# MiniPrinterController.net
KiCad netlist of a schematic drawn in EAGLE
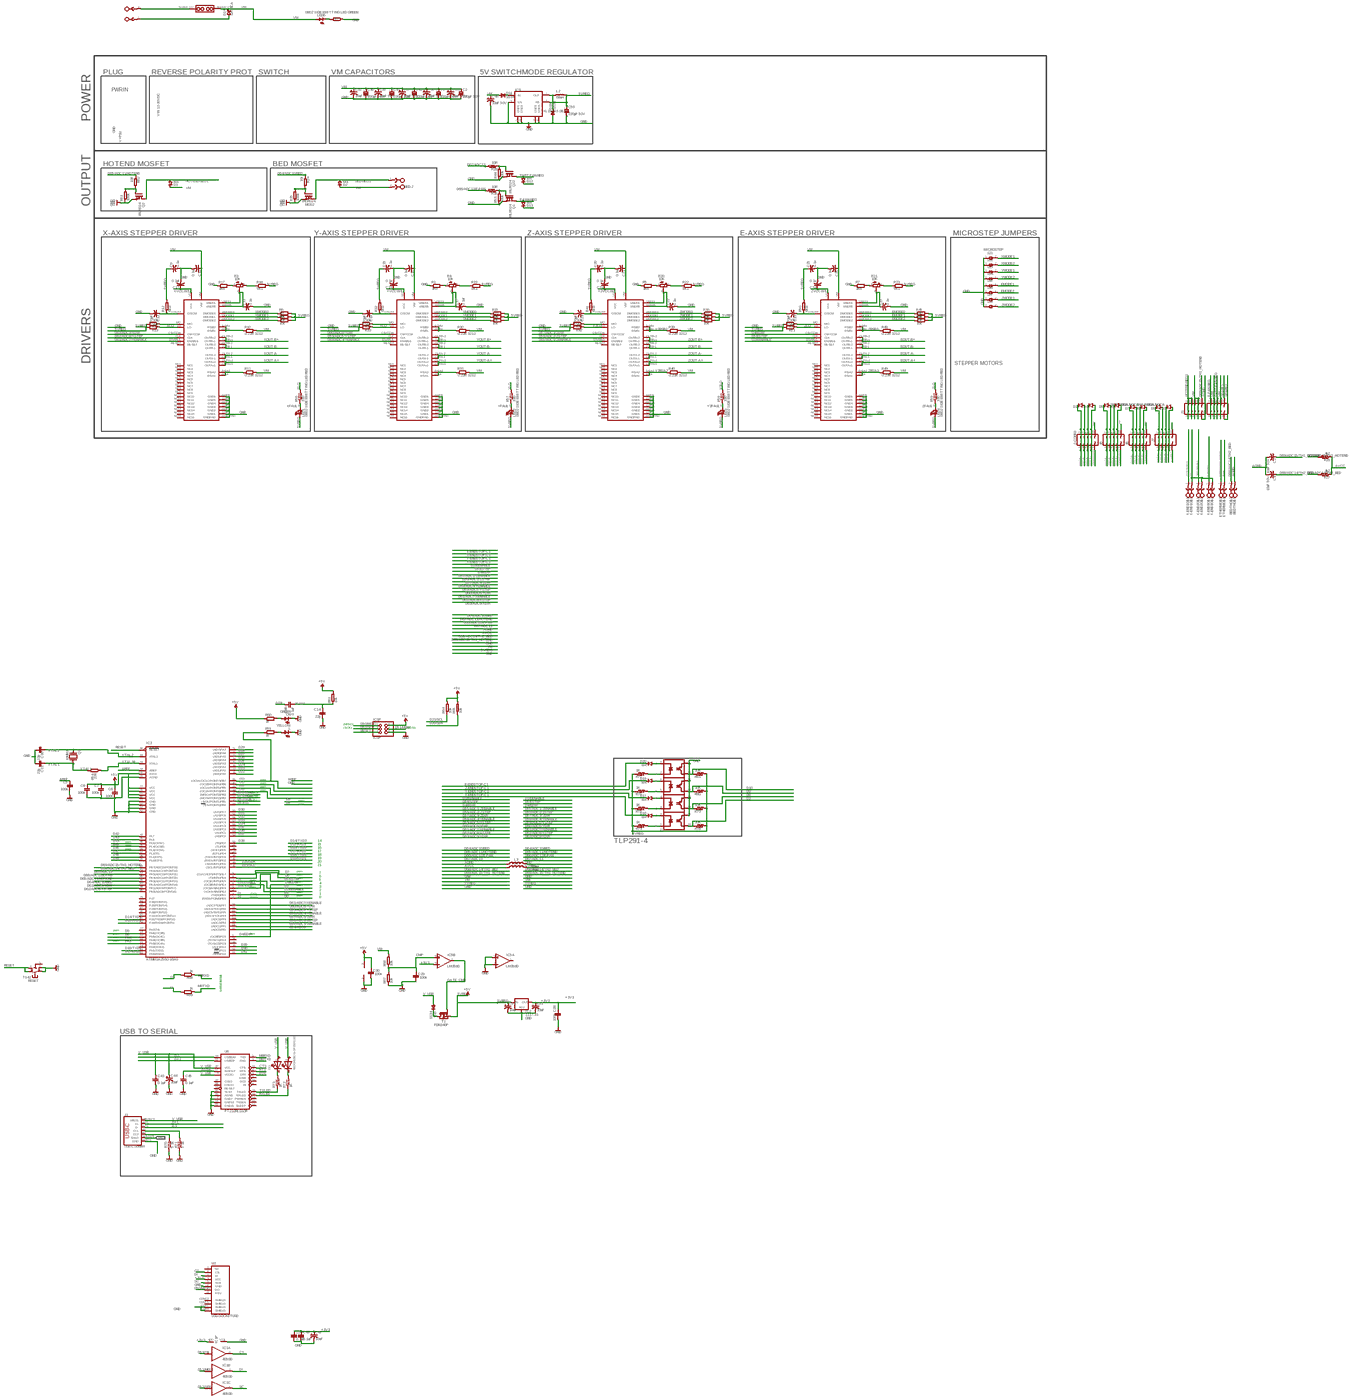
[diagram p0: schematic, sheet 1, overview]
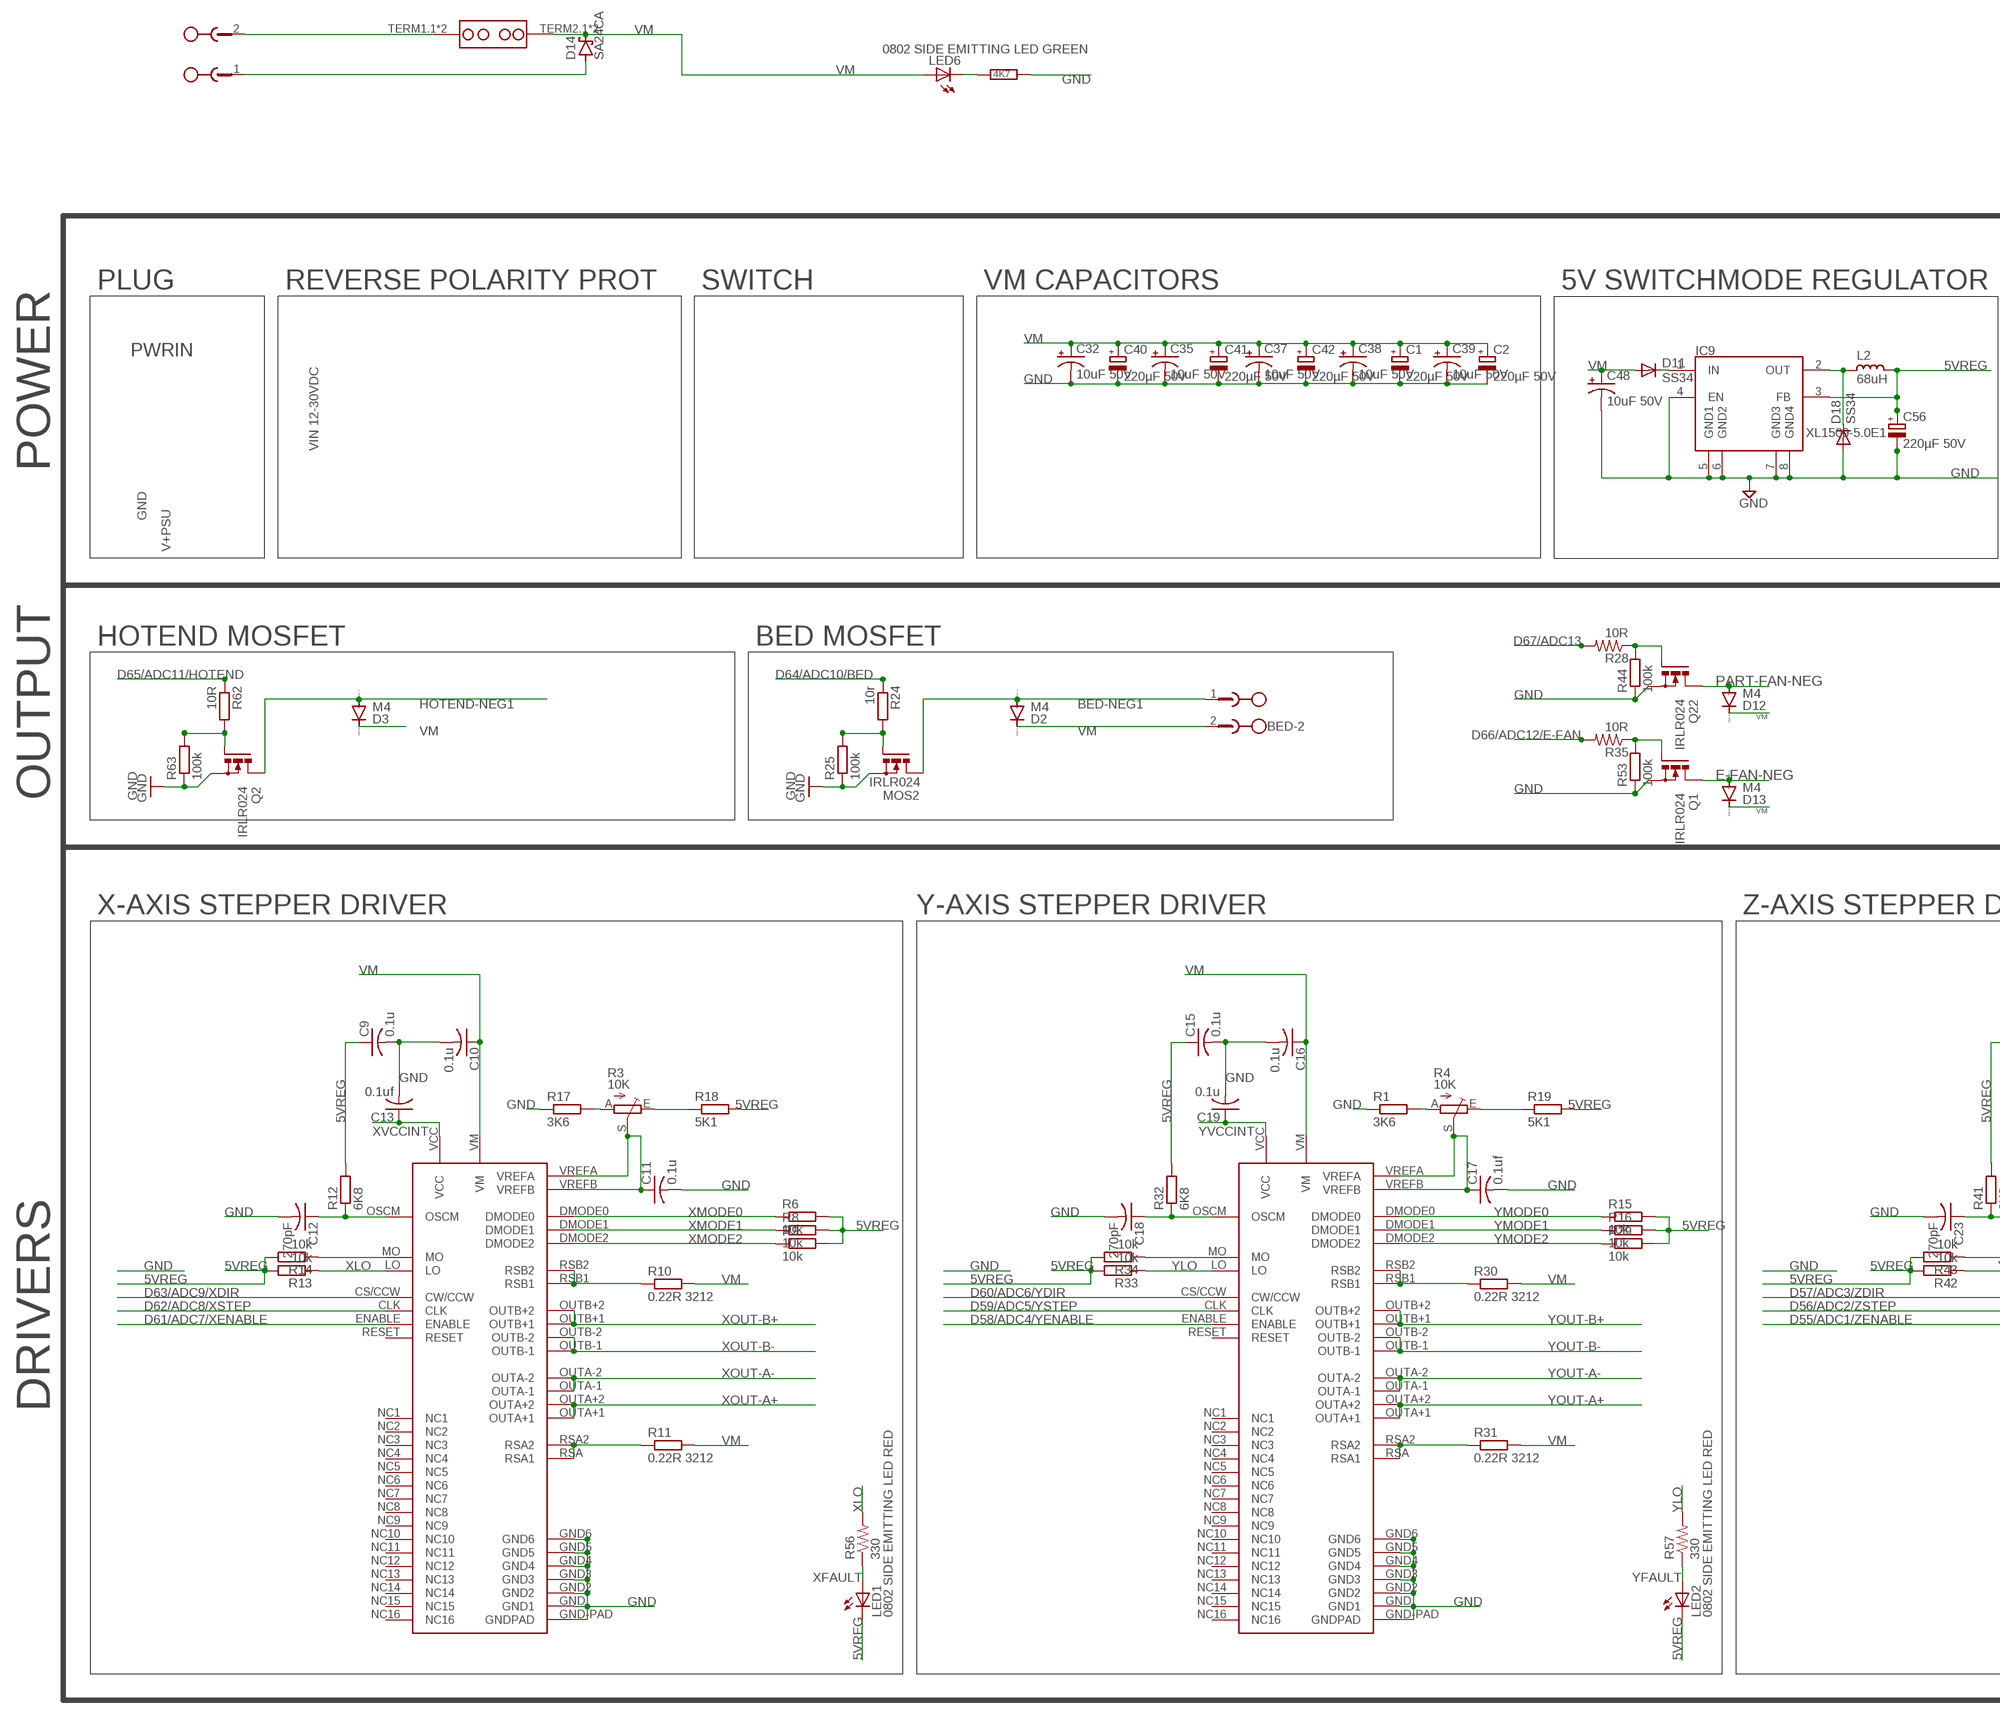
[diagram p1: schematic, sheet 1, part 1 of 7]
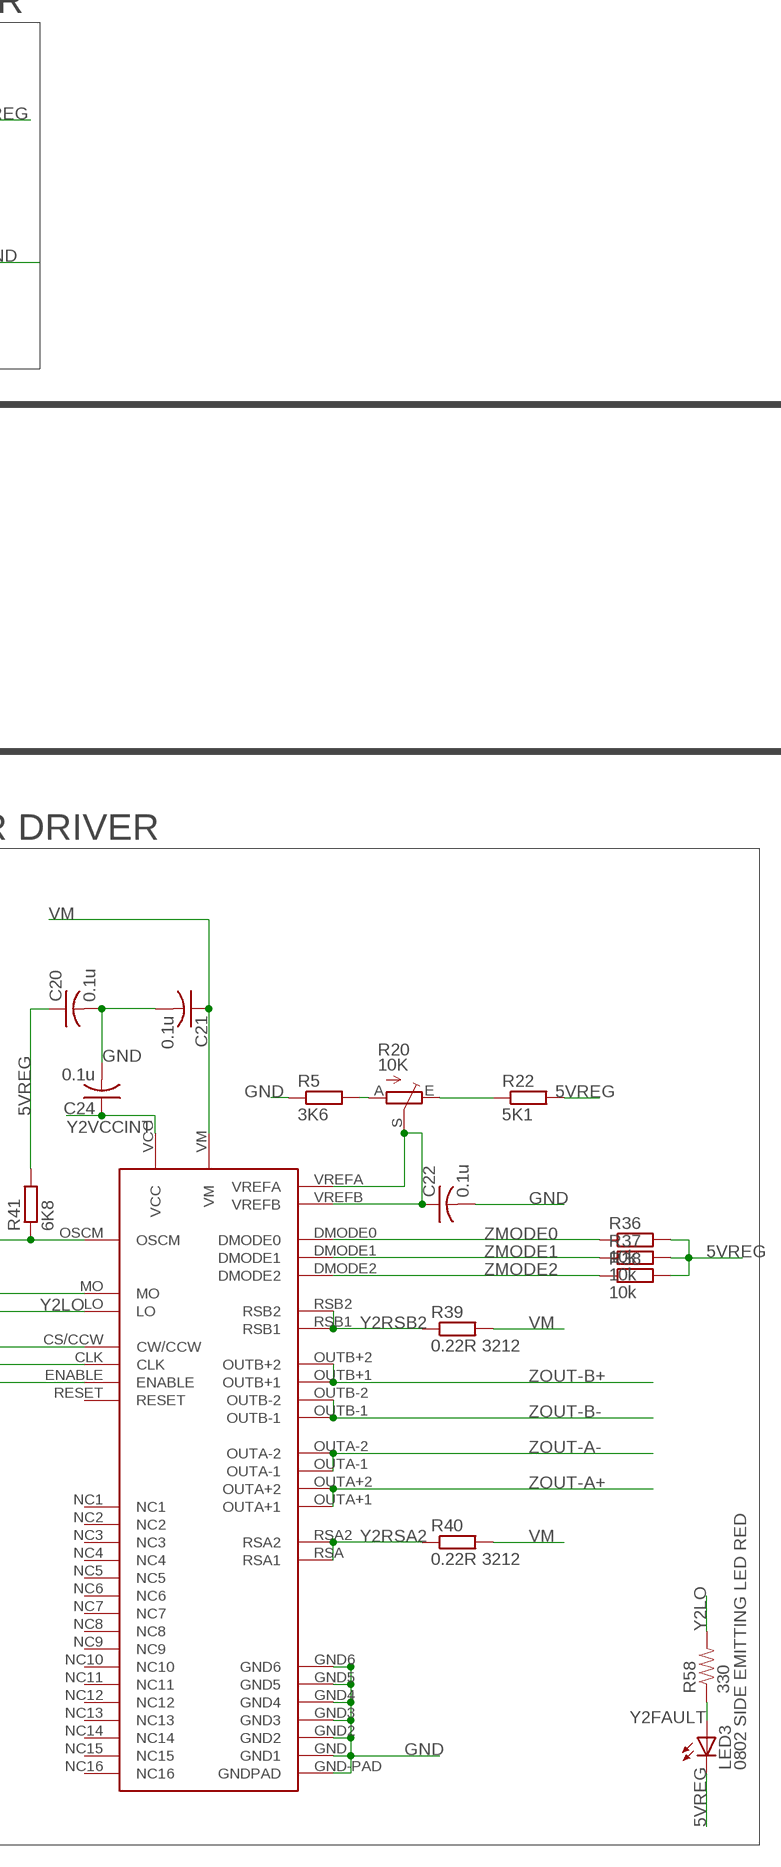
[diagram p2: schematic, sheet 1, part 2 of 7]
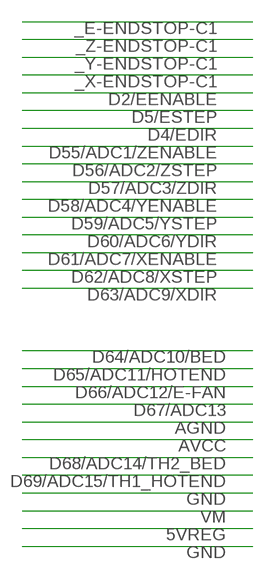
[diagram p3: schematic, sheet 1, part 3 of 7]
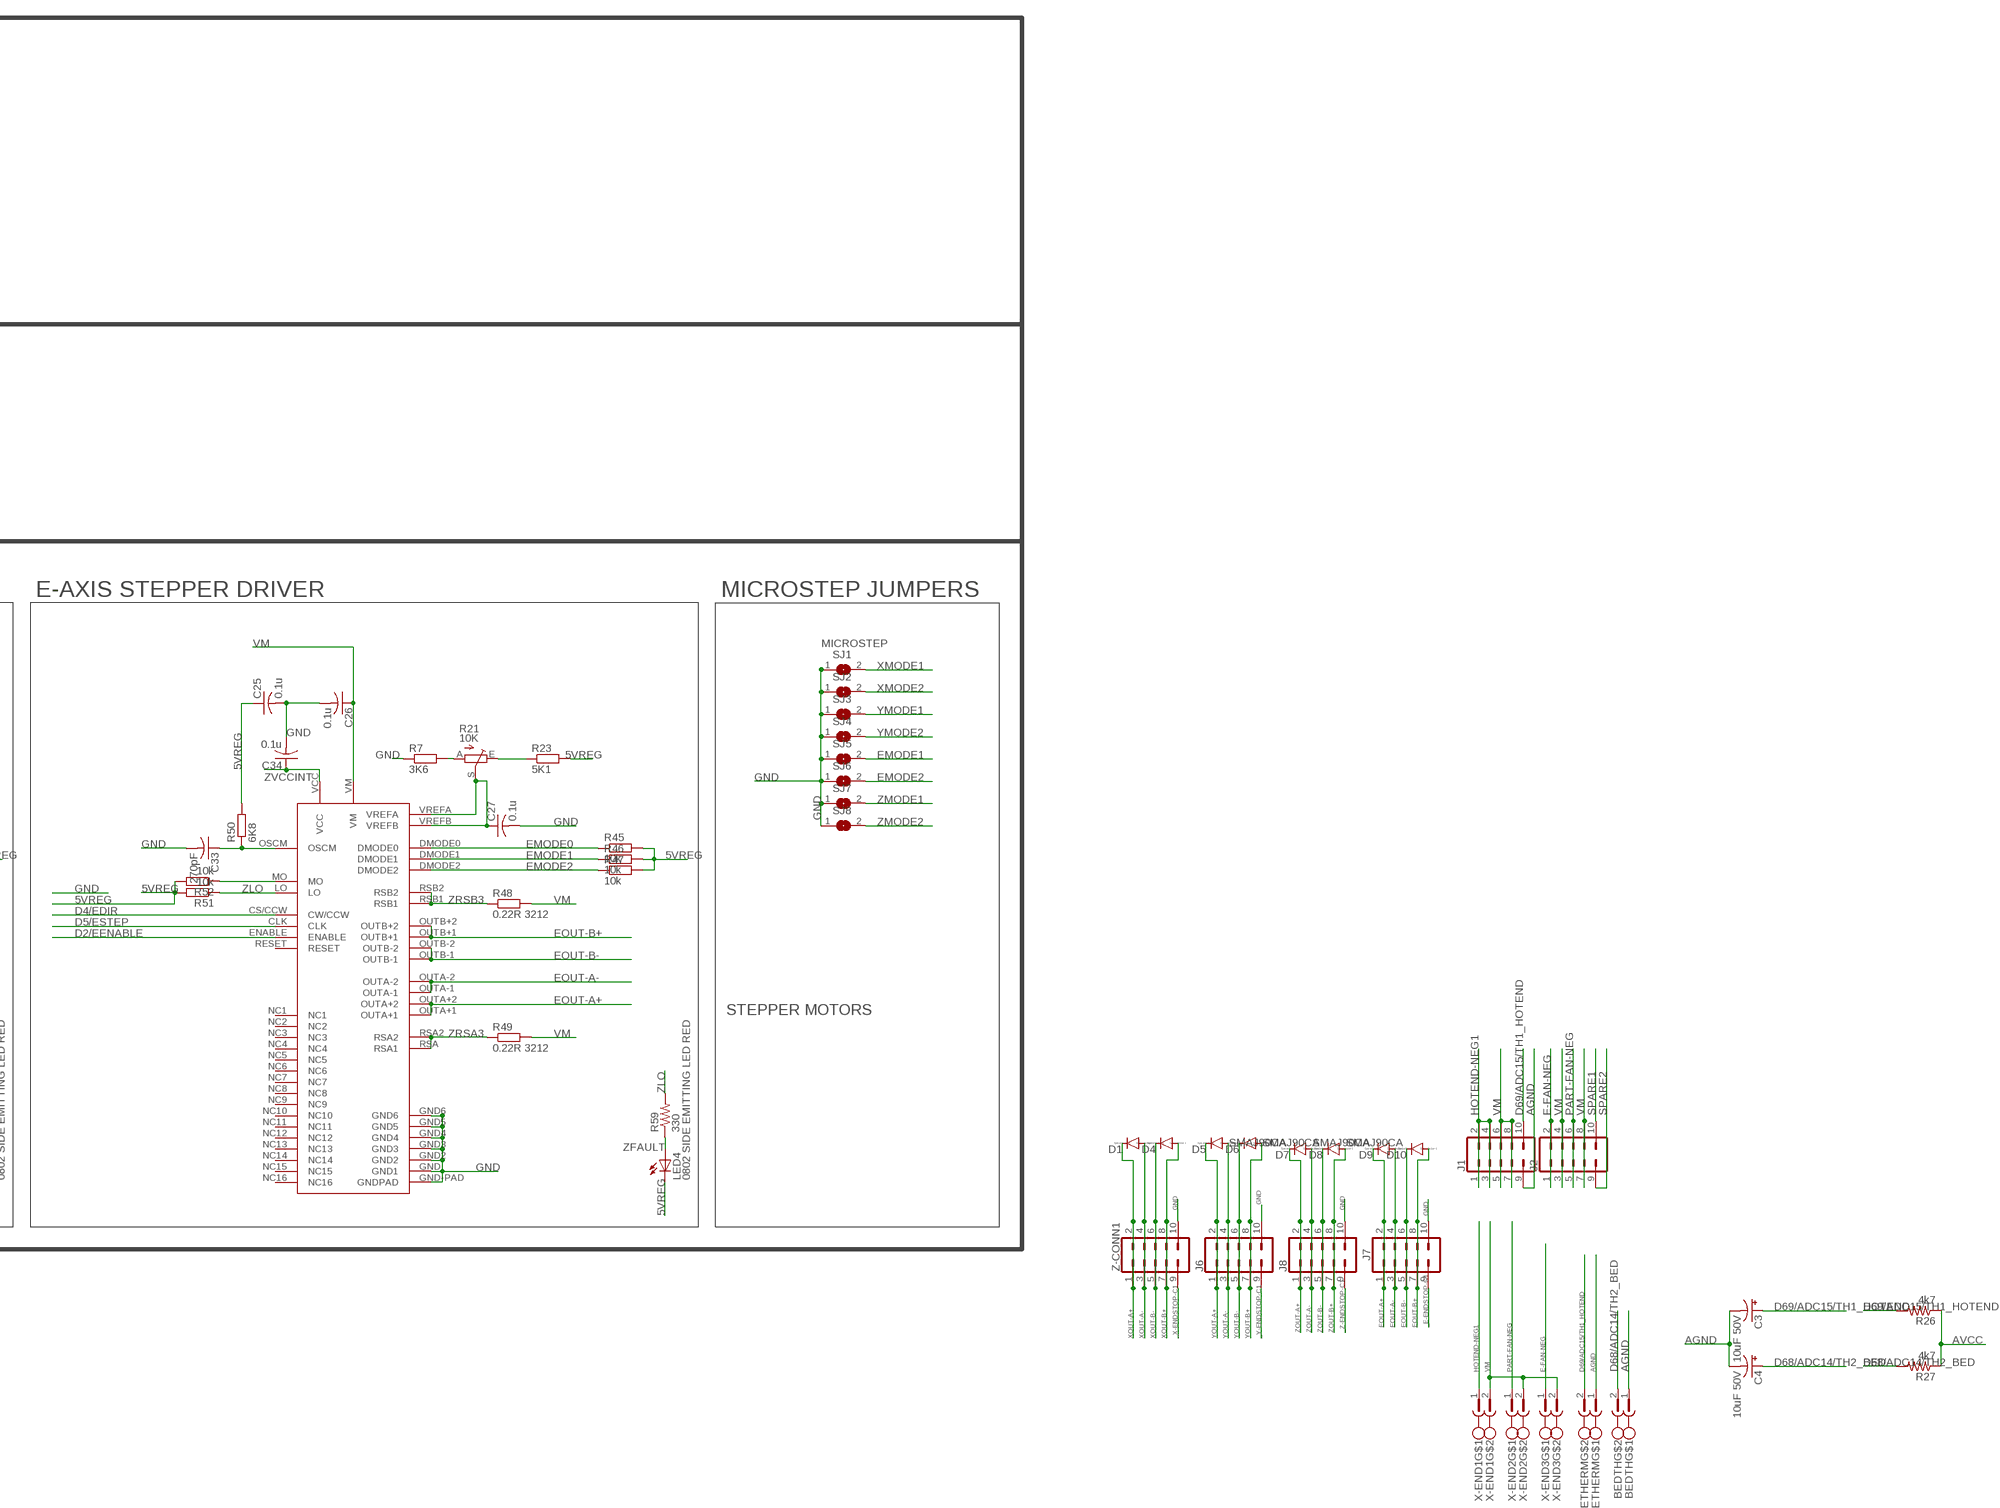
[diagram p4: schematic, sheet 1, part 4 of 7]
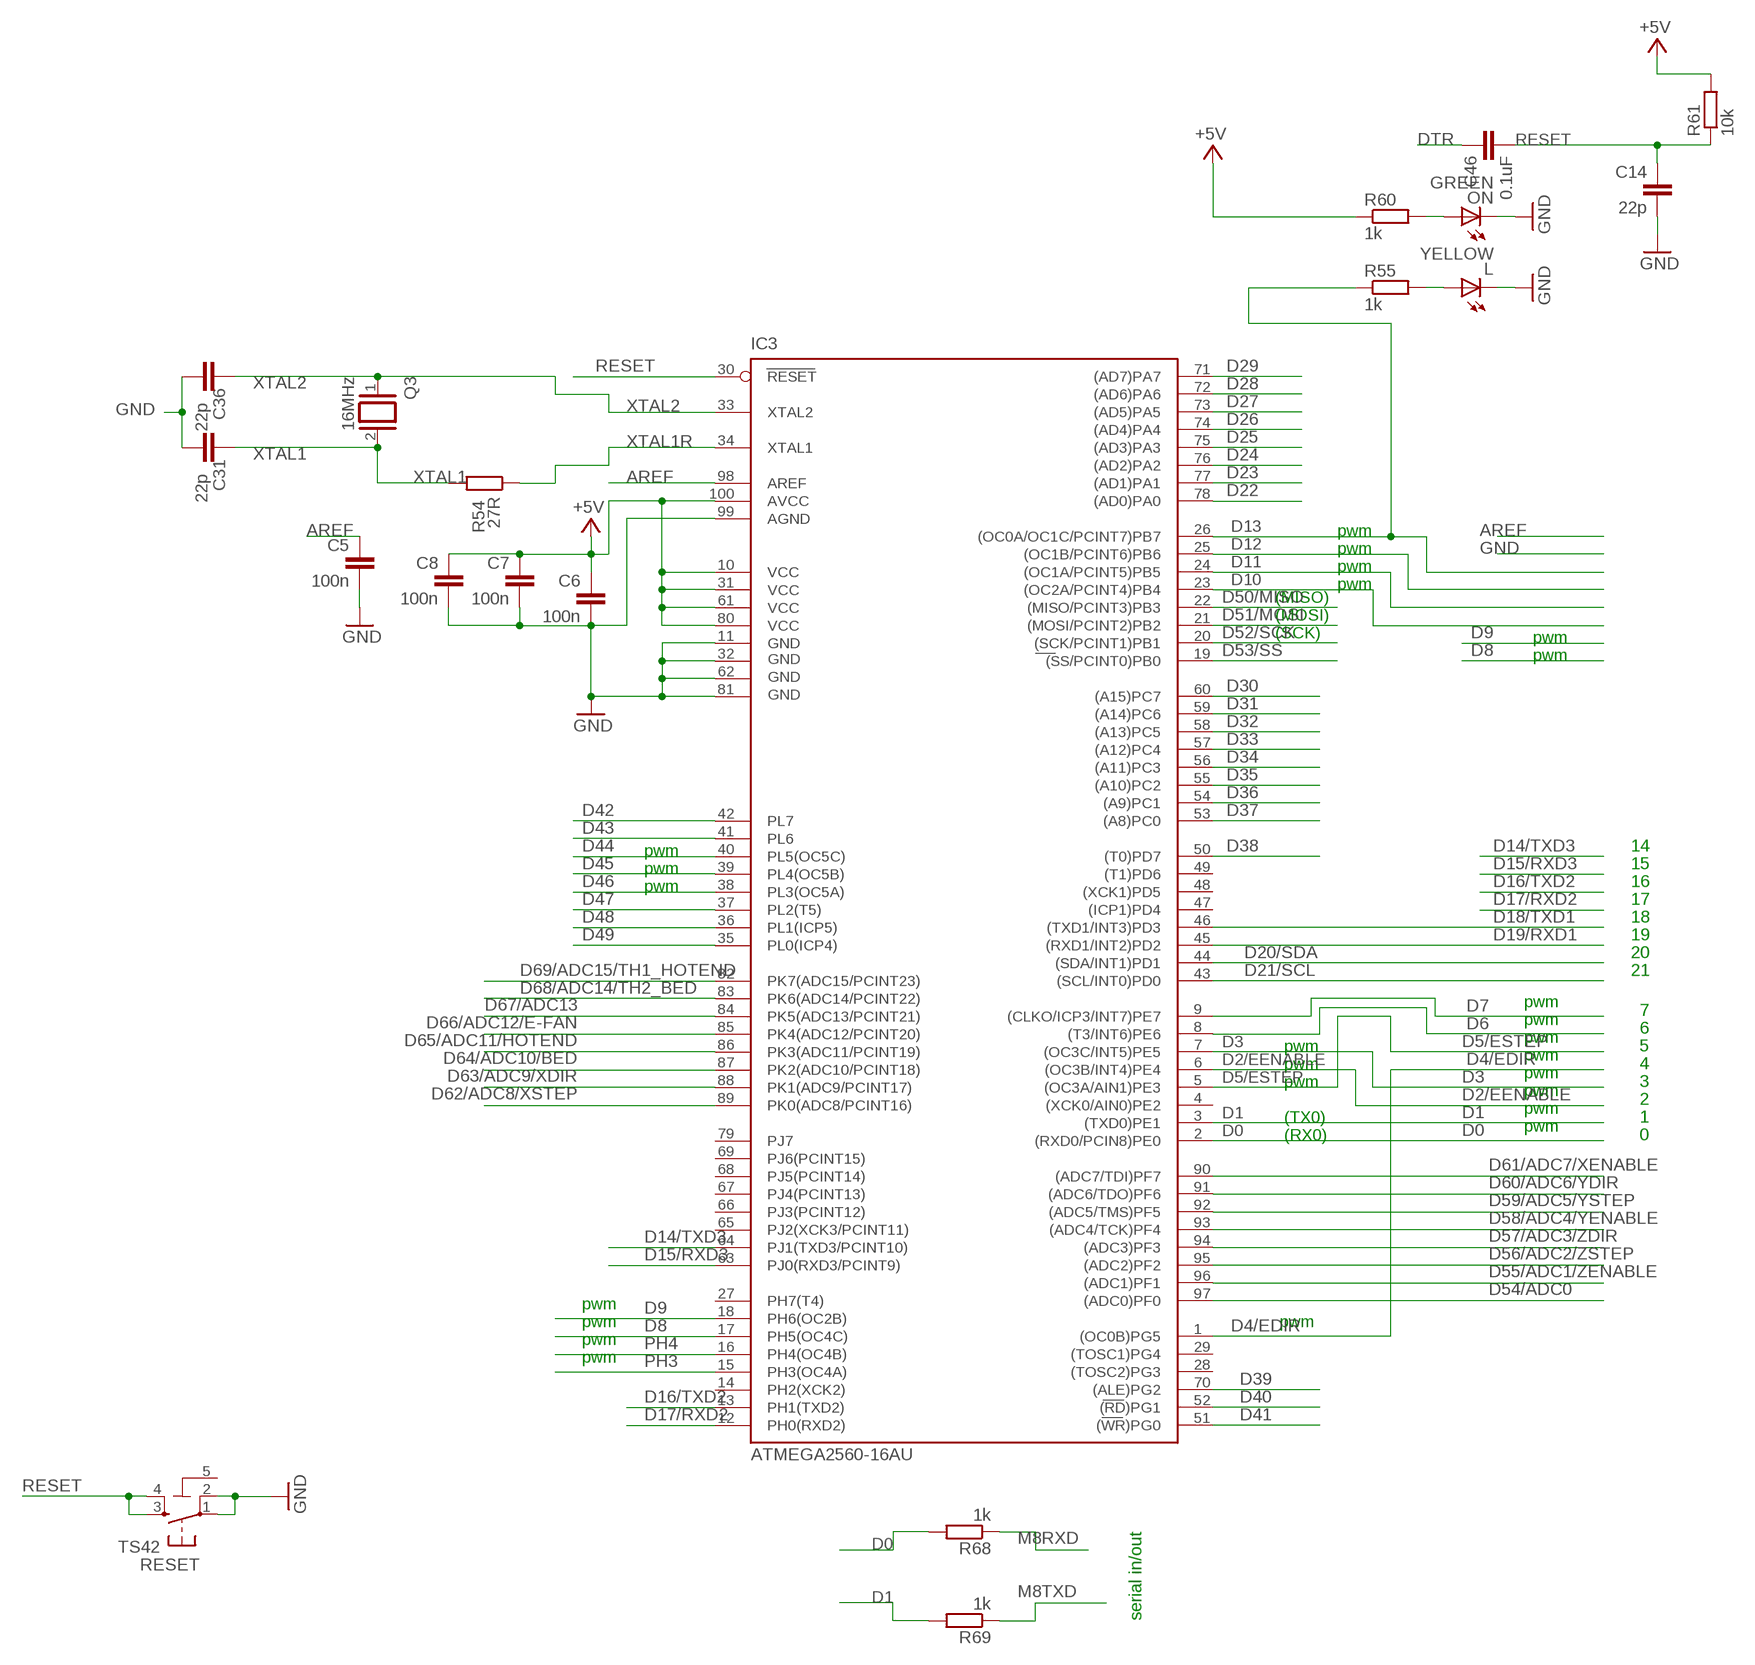
[diagram p5: schematic, sheet 1, part 5 of 7]
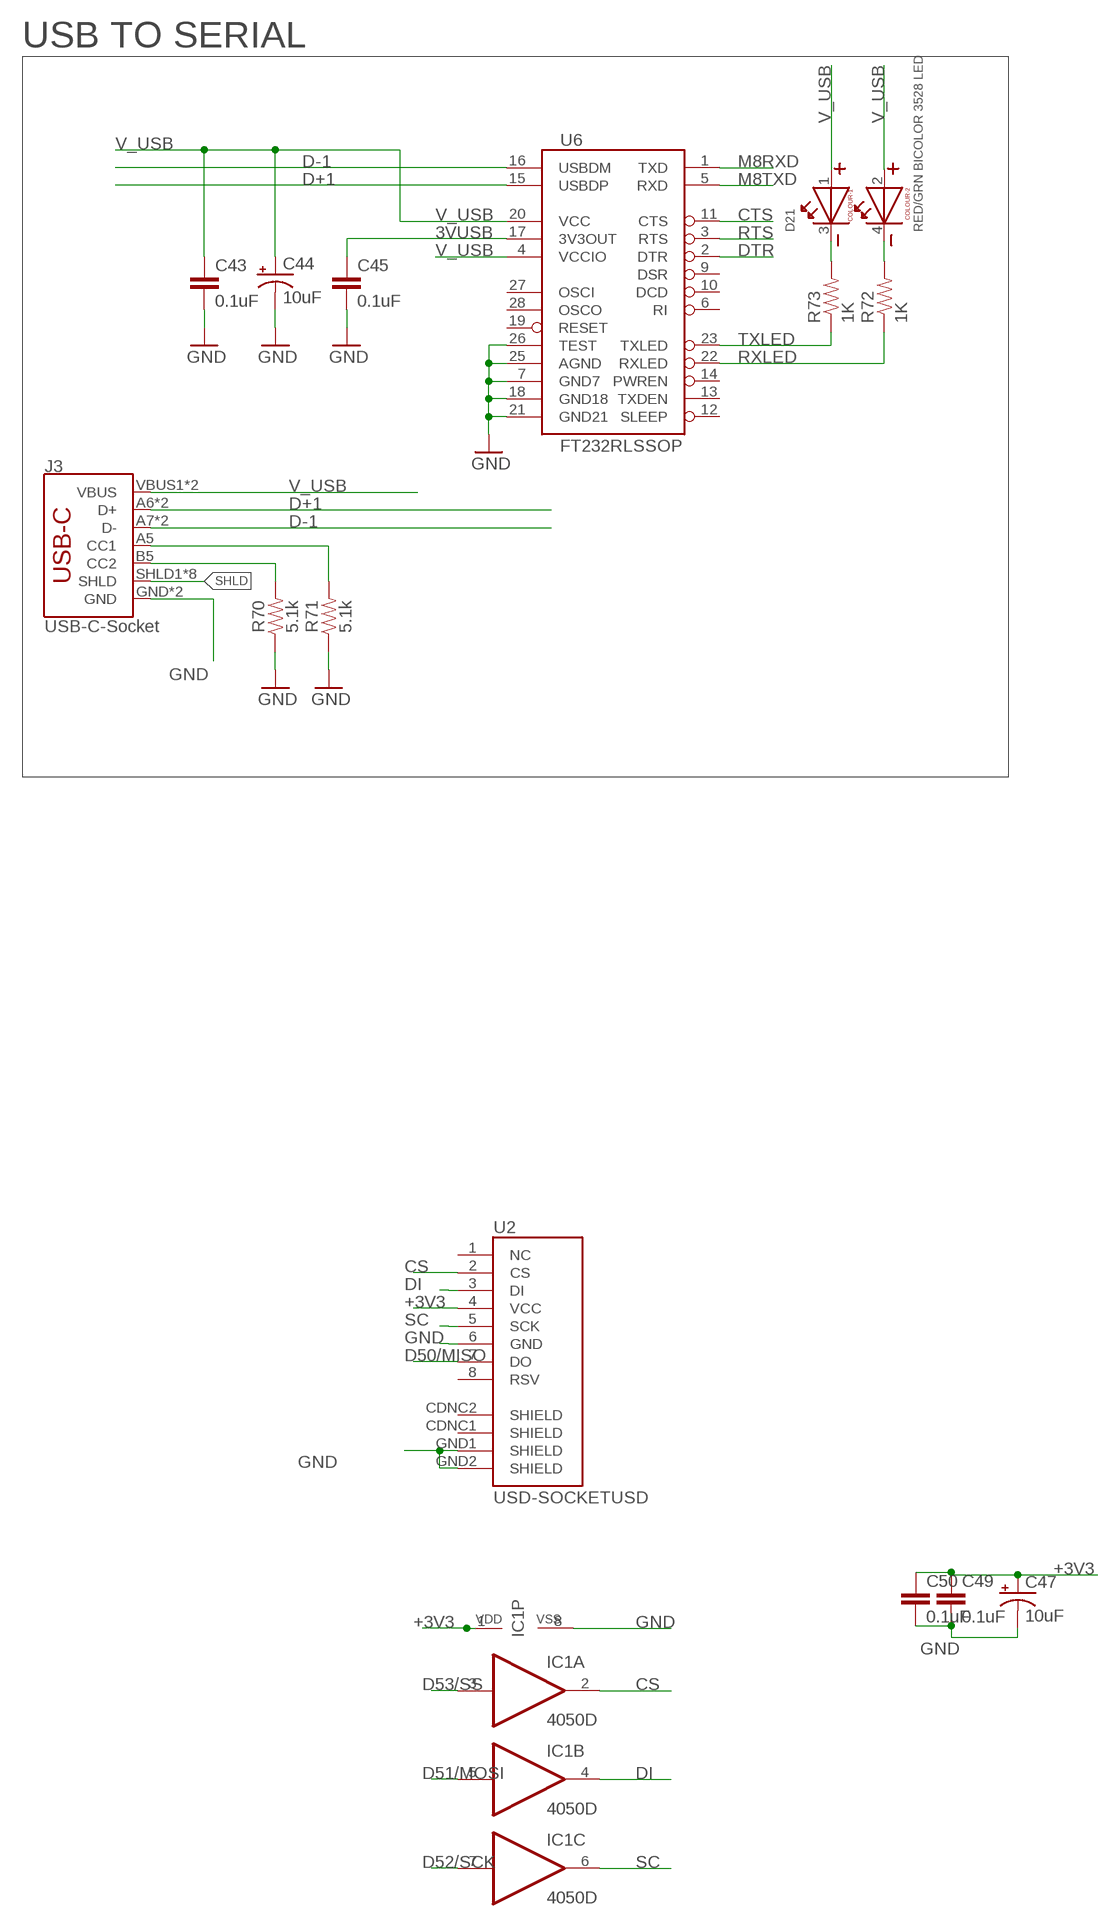
[diagram p6: schematic, sheet 1, part 6 of 7]
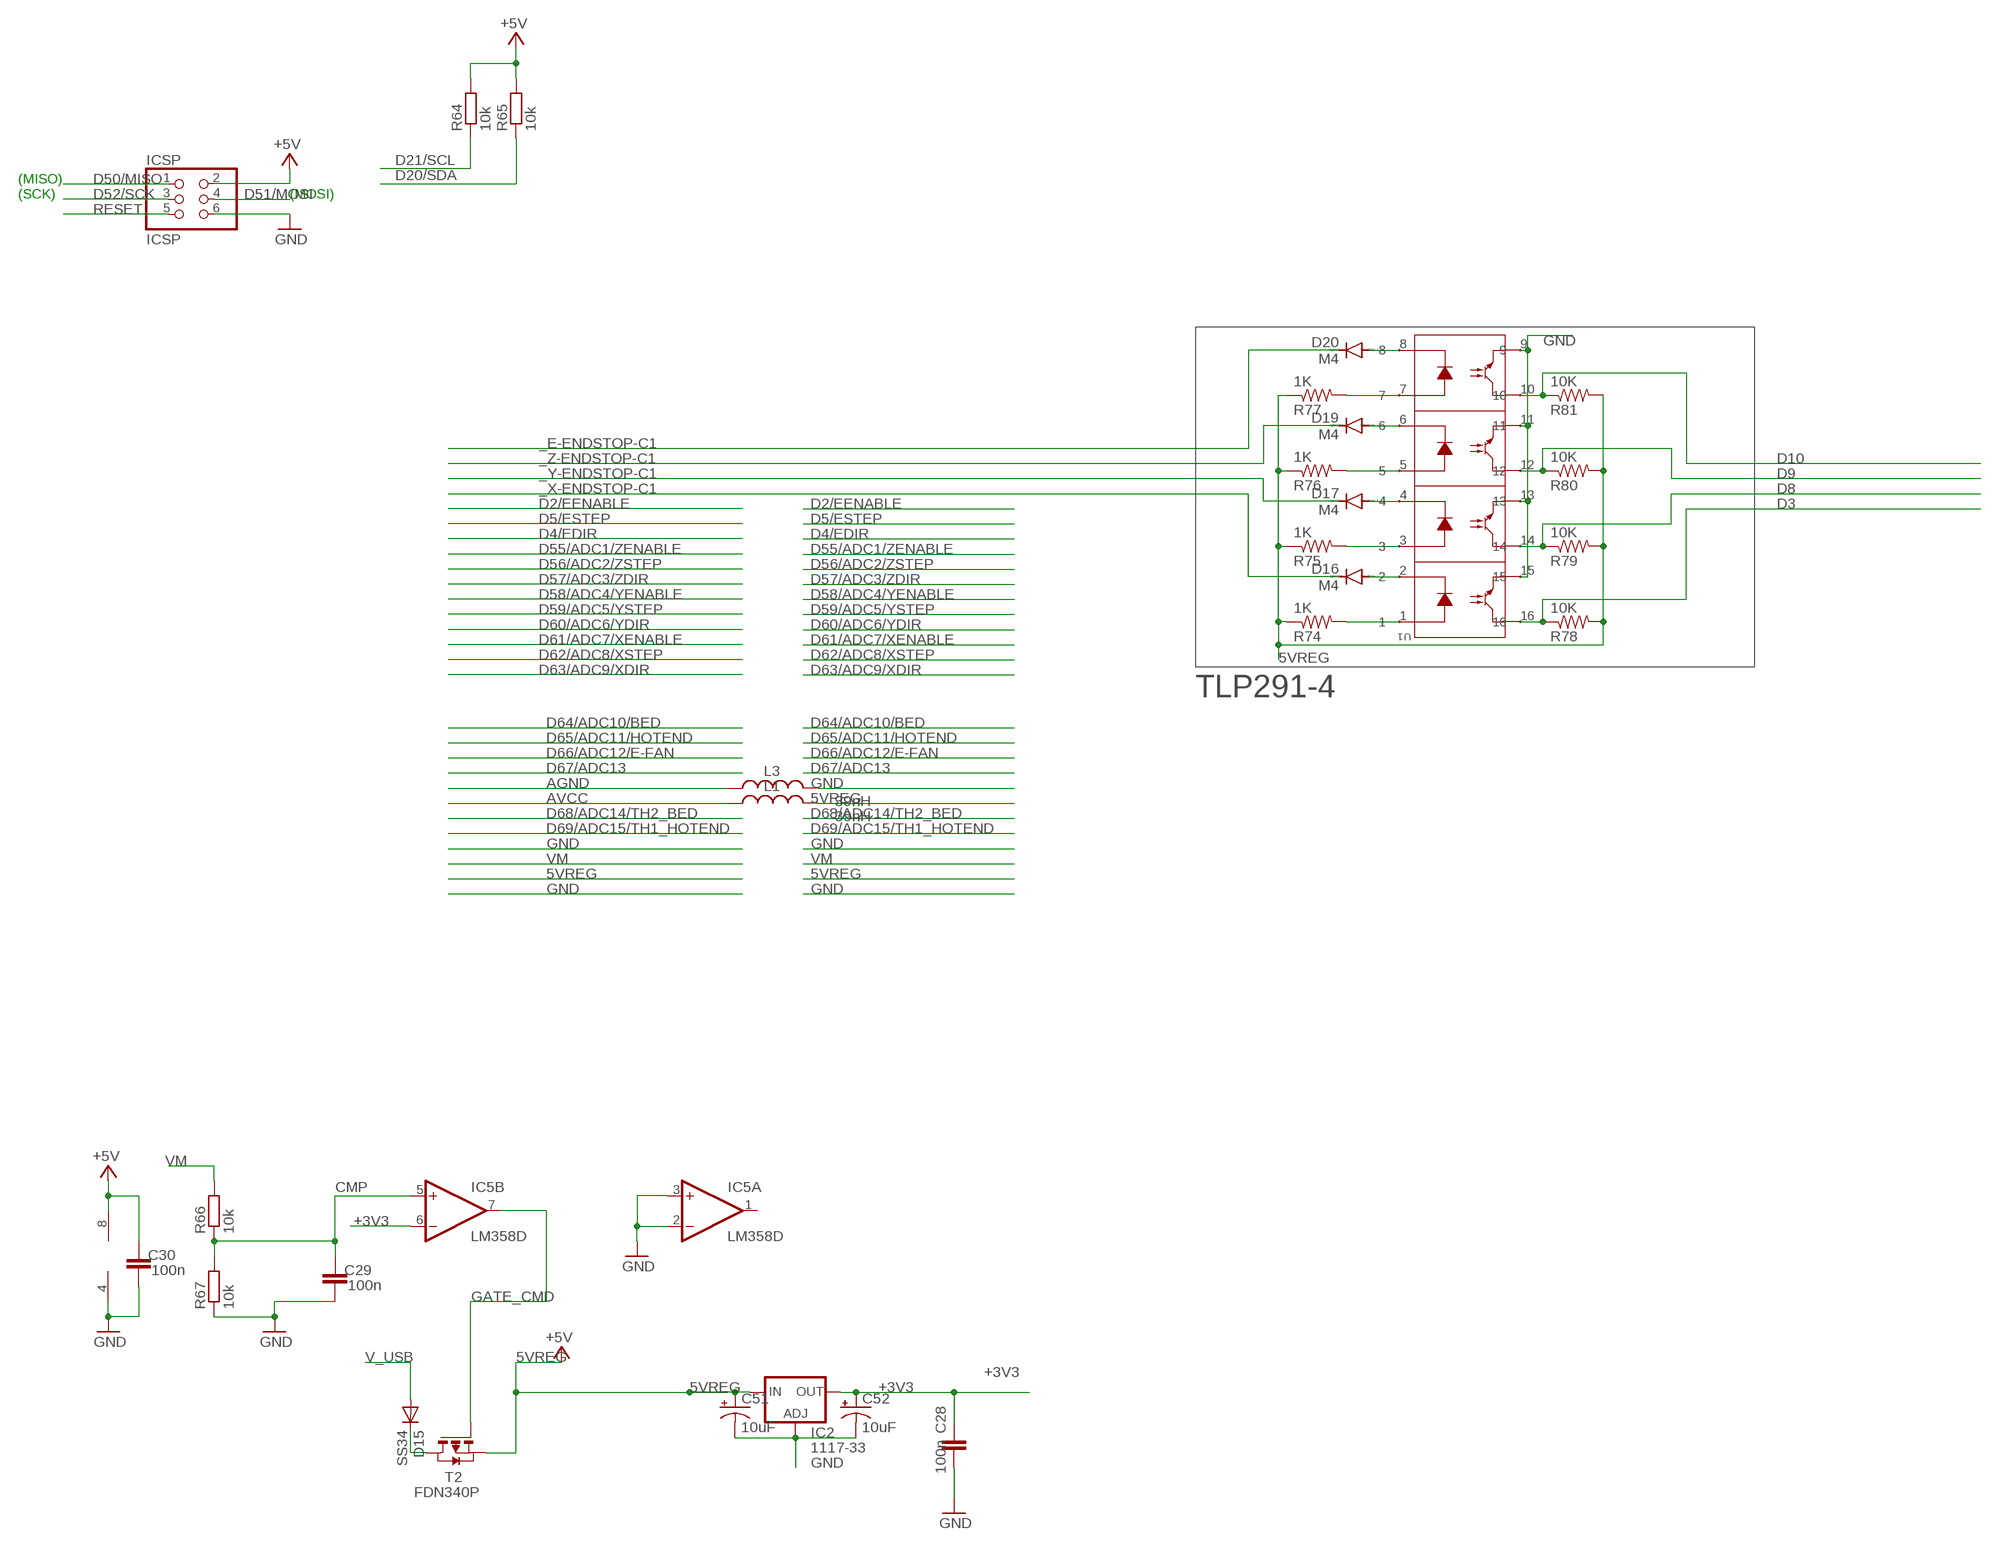
[diagram p7: schematic, sheet 1, part 7 of 7]

(export (version "E")
  (design (tool "Eeschema 10.0.6"))
  (components
    (comp (ref "BED")
      (value "Phoenix Pluggable 5.08mm 2 way")
      (footprint "eagle-import:MSTBA2")
      (fields (field (name "MF") "FARNELL") (field (name "MPN") "1757242"))
      (libsource (lib "eagle-import") (part "MSTBA2"))
    )
    (comp (ref "BEDTH")
      (value "Phoenix Pluggable 3.81mm 2 way")
      (footprint "eagle-import:MC1.5_2-G-3.81")
      (libsource (lib "eagle-import") (part "MC1.5/2"))
    )
    (comp (ref "C1")
      (value "220µF 50V")
      (footprint "eagle-import:E3,5-10")
      (libsource (lib "eagle-import") (part "CPOL-EUE3.5-10"))
    )
    (comp (ref "C2")
      (value "220µF 50V")
      (footprint "eagle-import:E3,5-10")
      (libsource (lib "eagle-import") (part "CPOL-EUE3.5-10"))
    )
    (comp (ref "C3")
      (value "10uF 50V")
      (footprint "eagle-import:EIA3216")
      (libsource (lib "eagle-import") (part "CAP_POL1206"))
    )
    (comp (ref "C4")
      (value "10uF 50V")
      (footprint "eagle-import:EIA3216")
      (libsource (lib "eagle-import") (part "CAP_POL1206"))
    )
    (comp (ref "C5")
      (value "100n")
      (footprint "eagle-import:C0603-ROUND")
      (libsource (lib "eagle-import") (part "C-EU0603-RND"))
    )
    (comp (ref "C6")
      (value "100n")
      (footprint "eagle-import:C0603-ROUND")
      (libsource (lib "eagle-import") (part "C-EU0603-RND"))
    )
    (comp (ref "C7")
      (value "100n")
      (footprint "eagle-import:C0603-ROUND")
      (libsource (lib "eagle-import") (part "C-EU0603-RND"))
    )
    (comp (ref "C8")
      (value "100n")
      (footprint "eagle-import:C0603-ROUND")
      (libsource (lib "eagle-import") (part "C-EU0603-RND"))
    )
    (comp (ref "C9")
      (value "0.1u")
      (footprint "eagle-import:C0603K")
      (libsource (lib "eagle-import") (part "C-USC0603K"))
    )
    (comp (ref "C10")
      (value "0.1u")
      (footprint "eagle-import:C0603K")
      (libsource (lib "eagle-import") (part "C-USC0603K"))
    )
    (comp (ref "C11")
      (value "0.1u")
      (footprint "eagle-import:C0603K")
      (libsource (lib "eagle-import") (part "C-USC0603K"))
    )
    (comp (ref "C12")
      (value "270pF")
      (footprint "eagle-import:C0603K")
      (libsource (lib "eagle-import") (part "C-USC0603K"))
    )
    (comp (ref "C13")
      (value "0.1uf")
      (footprint "eagle-import:C0603K")
      (libsource (lib "eagle-import") (part "C-USC0603K"))
    )
    (comp (ref "C14")
      (value "22p")
      (footprint "eagle-import:C0603-ROUND")
      (libsource (lib "eagle-import") (part "C-EU0603-RND"))
    )
    (comp (ref "C15")
      (value "0.1u")
      (footprint "eagle-import:C0603K")
      (libsource (lib "eagle-import") (part "C-USC0603K"))
    )
    (comp (ref "C16")
      (value "0.1u")
      (footprint "eagle-import:C0603K")
      (libsource (lib "eagle-import") (part "C-USC0603K"))
    )
    (comp (ref "C17")
      (value "0.1uf")
      (footprint "eagle-import:C0603K")
      (libsource (lib "eagle-import") (part "C-USC0603K"))
    )
    (comp (ref "C18")
      (value "270pF")
      (footprint "eagle-import:C0603K")
      (libsource (lib "eagle-import") (part "C-USC0603K"))
    )
    (comp (ref "C19")
      (value "0.1u")
      (footprint "eagle-import:C0603K")
      (libsource (lib "eagle-import") (part "C-USC0603K"))
    )
    (comp (ref "C20")
      (value "0.1u")
      (footprint "eagle-import:C0603K")
      (libsource (lib "eagle-import") (part "C-USC0603K"))
    )
    (comp (ref "C21")
      (value "0.1u")
      (footprint "eagle-import:C0603K")
      (libsource (lib "eagle-import") (part "C-USC0603K"))
    )
    (comp (ref "C22")
      (value "0.1u")
      (footprint "eagle-import:C0603K")
      (libsource (lib "eagle-import") (part "C-USC0603K"))
    )
    (comp (ref "C23")
      (value "270pF")
      (footprint "eagle-import:C0603K")
      (libsource (lib "eagle-import") (part "C-USC0603K"))
    )
    (comp (ref "C24")
      (value "0.1u")
      (footprint "eagle-import:C0603K")
      (libsource (lib "eagle-import") (part "C-USC0603K"))
    )
    (comp (ref "C25")
      (value "0.1u")
      (footprint "eagle-import:C0603K")
      (libsource (lib "eagle-import") (part "C-USC0603K"))
    )
    (comp (ref "C26")
      (value "0.1u")
      (footprint "eagle-import:C0603K")
      (libsource (lib "eagle-import") (part "C-USC0603K"))
    )
    (comp (ref "C27")
      (value "0.1u")
      (footprint "eagle-import:C0603K")
      (libsource (lib "eagle-import") (part "C-USC0603K"))
    )
    (comp (ref "C28")
      (value "100n")
      (footprint "eagle-import:C0603-ROUND")
      (libsource (lib "eagle-import") (part "C-EU0603-RND"))
    )
    (comp (ref "C29")
      (value "100n")
      (footprint "eagle-import:C0603-ROUND")
      (libsource (lib "eagle-import") (part "C-EU0603-RND"))
    )
    (comp (ref "C30")
      (value "100n")
      (footprint "eagle-import:C0603")
      (libsource (lib "eagle-import") (part "rcl_C-EUC0603"))
    )
    (comp (ref "C31")
      (value "22p")
      (footprint "eagle-import:C0603-ROUND")
      (libsource (lib "eagle-import") (part "C-EU0603-RND"))
    )
    (comp (ref "C32")
      (value "10uF 50V")
      (footprint "eagle-import:EIA3216")
      (libsource (lib "eagle-import") (part "CAP_POL1206"))
    )
    (comp (ref "C33")
      (value "270pF")
      (footprint "eagle-import:C0603K")
      (libsource (lib "eagle-import") (part "C-USC0603K"))
    )
    (comp (ref "C34")
      (value "0.1u")
      (footprint "eagle-import:C0603K")
      (libsource (lib "eagle-import") (part "C-USC0603K"))
    )
    (comp (ref "C35")
      (value "10uF 50V")
      (footprint "eagle-import:EIA3216")
      (libsource (lib "eagle-import") (part "CAP_POL1206"))
    )
    (comp (ref "C36")
      (value "22p")
      (footprint "eagle-import:C0603-ROUND")
      (libsource (lib "eagle-import") (part "C-EU0603-RND"))
    )
    (comp (ref "C37")
      (value "10uF 50V")
      (footprint "eagle-import:EIA3216")
      (libsource (lib "eagle-import") (part "CAP_POL1206"))
    )
    (comp (ref "C38")
      (value "10uF 50V")
      (footprint "eagle-import:EIA3216")
      (libsource (lib "eagle-import") (part "CAP_POL1206"))
    )
    (comp (ref "C39")
      (value "10uF 50V")
      (footprint "eagle-import:EIA3216")
      (libsource (lib "eagle-import") (part "CAP_POL1206"))
    )
    (comp (ref "C40")
      (value "220µF 50V")
      (footprint "eagle-import:E3,5-10")
      (libsource (lib "eagle-import") (part "CPOL-EUE3.5-10"))
    )
    (comp (ref "C41")
      (value "220µF 50V")
      (footprint "eagle-import:E3,5-10")
      (libsource (lib "eagle-import") (part "CPOL-EUE3.5-10"))
    )
    (comp (ref "C42")
      (value "220µF 50V")
      (footprint "eagle-import:E3,5-10")
      (libsource (lib "eagle-import") (part "CPOL-EUE3.5-10"))
    )
    (comp (ref "C43")
      (value "0.1uF")
      (footprint "eagle-import:0603-CAP")
      (libsource (lib "eagle-import") (part "CAP0603-CAP"))
    )
    (comp (ref "C44")
      (value "10uF")
      (footprint "eagle-import:EIA3216")
      (libsource (lib "eagle-import") (part "CAP_POL1206"))
    )
    (comp (ref "C45")
      (value "0.1uF")
      (footprint "eagle-import:0603-CAP")
      (libsource (lib "eagle-import") (part "CAP0603-CAP"))
    )
    (comp (ref "C46")
      (value "0.1uF")
      (footprint "eagle-import:C0603-ROUND")
      (libsource (lib "eagle-import") (part "C-EU0603-RND"))
    )
    (comp (ref "C47")
      (value "10uF")
      (footprint "eagle-import:EIA3216")
      (libsource (lib "eagle-import") (part "CAP_POL1206"))
    )
    (comp (ref "C48")
      (value "10uF 50V")
      (footprint "eagle-import:EIA3216")
      (libsource (lib "eagle-import") (part "CAP_POL1206"))
    )
    (comp (ref "C49")
      (value "0.1uF")
      (footprint "eagle-import:0603-CAP")
      (libsource (lib "eagle-import") (part "CAP0603-CAP"))
    )
    (comp (ref "C50")
      (value "0.1uF")
      (footprint "eagle-import:0603-CAP")
      (libsource (lib "eagle-import") (part "CAP0603-CAP"))
    )
    (comp (ref "C51")
      (value "10uF")
      (footprint "eagle-import:EIA3216")
      (libsource (lib "eagle-import") (part "CAP_POL1206"))
    )
    (comp (ref "C52")
      (value "10uF")
      (footprint "eagle-import:EIA3216")
      (libsource (lib "eagle-import") (part "CAP_POL1206"))
    )
    (comp (ref "C56")
      (value "220µF 50V")
      (footprint "eagle-import:E3,5-10")
      (libsource (lib "eagle-import") (part "CPOL-EUE3.5-10"))
    )
    (comp (ref "D1")
      (value "SMAJ90CA")
      (footprint "eagle-import:DO-214AC")
      (libsource (lib "eagle-import") (part "DIODE-DO-214AC"))
    )
    (comp (ref "D2")
      (value "M4")
      (footprint "eagle-import:DO-214AC")
      (libsource (lib "eagle-import") (part "DIODE-DO-214AC"))
    )
    (comp (ref "D3")
      (value "M4")
      (footprint "eagle-import:DO-214AC")
      (libsource (lib "eagle-import") (part "DIODE-DO-214AC"))
    )
    (comp (ref "D4")
      (value "SMAJ90CA")
      (footprint "eagle-import:DO-214AC")
      (libsource (lib "eagle-import") (part "DIODE-DO-214AC"))
    )
    (comp (ref "D5")
      (value "SMAJ90CA")
      (footprint "eagle-import:DO-214AC")
      (libsource (lib "eagle-import") (part "DIODE-DO-214AC"))
    )
    (comp (ref "D6")
      (value "SMAJ90CA")
      (footprint "eagle-import:DO-214AC")
      (libsource (lib "eagle-import") (part "DIODE-DO-214AC"))
    )
    (comp (ref "D7")
      (value "SMAJ90CA")
      (footprint "eagle-import:DO-214AC")
      (libsource (lib "eagle-import") (part "DIODE-DO-214AC"))
    )
    (comp (ref "D8")
      (value "SMAJ90CA")
      (footprint "eagle-import:DO-214AC")
      (libsource (lib "eagle-import") (part "DIODE-DO-214AC"))
    )
    (comp (ref "D9")
      (value "SMAJ90CA")
      (footprint "eagle-import:DO-214AC")
      (libsource (lib "eagle-import") (part "DIODE-DO-214AC"))
    )
    (comp (ref "D10")
      (value "SMAJ90CA")
      (footprint "eagle-import:DO-214AC")
      (libsource (lib "eagle-import") (part "DIODE-DO-214AC"))
    )
    (comp (ref "D11")
      (value "SS34")
      (footprint "eagle-import:DO-214AC")
      (libsource (lib "eagle-import") (part "dp_devices_DIODE-DO-214AC"))
    )
    (comp (ref "D12")
      (value "M4")
      (footprint "eagle-import:DO-214AC")
      (libsource (lib "eagle-import") (part "DIODE-DO-214AC"))
    )
    (comp (ref "D13")
      (value "M4")
      (footprint "eagle-import:DO-214AC")
      (libsource (lib "eagle-import") (part "DIODE-DO-214AC"))
    )
    (comp (ref "D14")
      (value "SA24CA")
      (footprint "eagle-import:C4111-15")
      (libsource (lib "eagle-import") (part "1N6267A"))
    )
    (comp (ref "D15")
      (value "SS34")
      (footprint "eagle-import:DO-214AC")
      (libsource (lib "eagle-import") (part "dp_devices_DIODE-DO-214AC"))
    )
    (comp (ref "D16")
      (value "M4")
      (footprint "eagle-import:DO-214AC")
      (libsource (lib "eagle-import") (part "DIODE-DO-214AC"))
    )
    (comp (ref "D17")
      (value "M4")
      (footprint "eagle-import:DO-214AC")
      (libsource (lib "eagle-import") (part "DIODE-DO-214AC"))
    )
    (comp (ref "D18")
      (value "SS34")
      (footprint "eagle-import:DO-214AC")
      (libsource (lib "eagle-import") (part "dp_devices_DIODE-DO-214AC"))
    )
    (comp (ref "D19")
      (value "M4")
      (footprint "eagle-import:DO-214AC")
      (libsource (lib "eagle-import") (part "DIODE-DO-214AC"))
    )
    (comp (ref "D20")
      (value "M4")
      (footprint "eagle-import:DO-214AC")
      (libsource (lib "eagle-import") (part "DIODE-DO-214AC"))
    )
    (comp (ref "D21")
      (value "RED/GRN BICOLOR 3528 LED")
      (footprint "eagle-import:3528")
      (fields
        (field (name "MANUFACTURER") "Würth Elektronik eiSos GmbH")
        (field (name "CREATED-BY") "Christin Otto")
      )
      (libsource (lib "eagle-import") (part "WL-SBTW-150141RB73100-R&B"))
    )
    (comp (ref "ETHERM")
      (value "Phoenix Pluggable 3.81mm 2 way")
      (footprint "eagle-import:MC1.5_2-G-3.81")
      (libsource (lib "eagle-import") (part "MC1.5/2"))
    )
    (comp (ref "IC1")
      (value "4050D")
      (footprint "eagle-import:SO16")
      (libsource (lib "eagle-import") (part "4050D"))
    )
    (comp (ref "IC2")
      (value "1117-33")
      (footprint "eagle-import:SOT223")
      (libsource (lib "eagle-import") (part "LD117A?S33TR"))
    )
    (comp (ref "IC3")
      (value "ATMEGA2560-16AU")
      (footprint "eagle-import:TQFP100")
      (libsource (lib "eagle-import") (part "ATMEGAAU1280-16"))
    )
    (comp (ref "IC5")
      (value "LM358D")
      (footprint "eagle-import:SO08")
      (libsource (lib "eagle-import") (part "LM358D"))
    )
    (comp (ref "IC9")
      (value "XL1509-5.0E1")
      (footprint "eagle-import:SO08")
      (libsource (lib "eagle-import") (part "XL1509"))
    )
    (comp (ref "ICSP")
      (value "ICSP")
      (footprint "eagle-import:2X03")
      (libsource (lib "eagle-import") (part "PINHD-2X3"))
    )
    (comp (ref "J1")
      (value "CONN_05X2SHD_LOCK")
      (footprint "eagle-import:2X5-SHROUDED_LOCK")
      (libsource (lib "eagle-import") (part "CONN_05X2SHD_LOCK"))
    )
    (comp (ref "J2")
      (value "CONN_05X2SHD_LOCK")
      (footprint "eagle-import:2X5-SHROUDED_LOCK")
      (libsource (lib "eagle-import") (part "CONN_05X2SHD_LOCK"))
    )
    (comp (ref "J3")
      (value "USB-C-Socket")
      (footprint "eagle-import:USB-C-16P")
      (libsource (lib "eagle-import") (part "USB_C16PIN"))
    )
    (comp (ref "J6")
      (value "CONN_05X2SHD_LOCK")
      (footprint "eagle-import:2X5-SHROUDED_LOCK")
      (libsource (lib "eagle-import") (part "CONN_05X2SHD_LOCK"))
    )
    (comp (ref "J7")
      (value "CONN_05X2SHD_LOCK")
      (footprint "eagle-import:2X5-SHROUDED_LOCK")
      (libsource (lib "eagle-import") (part "CONN_05X2SHD_LOCK"))
    )
    (comp (ref "J8")
      (value "CONN_05X2SHD_LOCK")
      (footprint "eagle-import:2X5-SHROUDED_LOCK")
      (libsource (lib "eagle-import") (part "CONN_05X2SHD_LOCK"))
    )
    (comp (ref "L")
      (value "YELLOW")
      (footprint "eagle-import:CHIP-LED0805")
      (libsource (lib "eagle-import") (part "led_LEDCHIP-LED0805"))
    )
    (comp (ref "L1")
      (value "39nH")
      (footprint "eagle-import:0603")
      (libsource (lib "eagle-import") (part "INDUCTOR0603"))
    )
    (comp (ref "L2")
      (value "68uH")
      (footprint "eagle-import:CD75")
      (libsource (lib "eagle-import") (part "L_CD75"))
    )
    (comp (ref "L3")
      (value "39nH")
      (footprint "eagle-import:0603")
      (libsource (lib "eagle-import") (part "INDUCTOR0603"))
    )
    (comp (ref "LED1")
      (value "0802 SIDE EMITTING LED RED")
      (footprint "eagle-import:CHIPLED_0805")
      (libsource (lib "eagle-import") (part "LEDCHIPLED_0805"))
    )
    (comp (ref "LED2")
      (value "0802 SIDE EMITTING LED RED")
      (footprint "eagle-import:CHIPLED_0805")
      (libsource (lib "eagle-import") (part "LEDCHIPLED_0805"))
    )
    (comp (ref "LED3")
      (value "0802 SIDE EMITTING LED RED")
      (footprint "eagle-import:CHIPLED_0805")
      (libsource (lib "eagle-import") (part "LEDCHIPLED_0805"))
    )
    (comp (ref "LED4")
      (value "0802 SIDE EMITTING LED RED")
      (footprint "eagle-import:CHIPLED_0805")
      (libsource (lib "eagle-import") (part "LEDCHIPLED_0805"))
    )
    (comp (ref "LED6")
      (value "0802 SIDE EMITTING LED GREEN")
      (footprint "eagle-import:LED3MM")
      (libsource (lib "eagle-import") (part "LED3MM"))
    )
    (comp (ref "MOS2")
      (value "IRLR024")
      (footprint "eagle-import:D2PACK")
      (libsource (lib "eagle-import") (part "N-POWER-MOSFETD2PAK-MOSFET"))
    )
    (comp (ref "ON")
      (value "GREEN")
      (footprint "eagle-import:CHIP-LED0805")
      (libsource (lib "eagle-import") (part "led_LEDCHIP-LED0805"))
    )
    (comp (ref "PWRIN")
      (value "Phoenix Pluggable 5.08mm 2 way")
      (footprint "eagle-import:MSTBA2")
      (fields (field (name "MF") "FARNELL") (field (name "MPN") "1757242"))
      (libsource (lib "eagle-import") (part "MSTBA2"))
    )
    (comp (ref "Q1")
      (value "IRLR024")
      (footprint "eagle-import:D-PAK_TO252AA")
      (libsource (lib "eagle-import") (part "N-POWER-MOSFETDPAK-MOSFET"))
    )
    (comp (ref "Q2")
      (value "IRLR024")
      (footprint "eagle-import:D-PAK_TO252AA")
      (libsource (lib "eagle-import") (part "N-POWER-MOSFETDPAK-MOSFET"))
    )
    (comp (ref "Q3")
      (value "16MHz")
      (footprint "eagle-import:QS")
      (libsource (lib "eagle-import") (part "XTAL/S"))
    )
    (comp (ref "Q22")
      (value "IRLR024")
      (footprint "eagle-import:D-PAK_TO252AA")
      (libsource (lib "eagle-import") (part "N-POWER-MOSFETDPAK-MOSFET"))
    )
    (comp (ref "R1")
      (value "3K6")
      (footprint "eagle-import:R0603")
      (libsource (lib "eagle-import") (part "resistor_348_R-EU_R0603"))
    )
    (comp (ref "R2")
      (value "4K7")
      (footprint "eagle-import:R0603")
      (libsource (lib "eagle-import") (part "rcl_R-EU_R0603"))
    )
    (comp (ref "R3")
      (value "10K")
      (footprint "eagle-import:B25P")
      (libsource (lib "eagle-import") (part "TRIM_EU-B25P"))
    )
    (comp (ref "R4")
      (value "10K")
      (footprint "eagle-import:B25P")
      (libsource (lib "eagle-import") (part "TRIM_EU-B25P"))
    )
    (comp (ref "R5")
      (value "3K6")
      (footprint "eagle-import:R0603")
      (libsource (lib "eagle-import") (part "resistor_348_R-EU_R0603"))
    )
    (comp (ref "R6")
      (value "10k")
      (footprint "eagle-import:R0603")
      (libsource (lib "eagle-import") (part "resistor_348_R-EU_R0603"))
    )
    (comp (ref "R7")
      (value "3K6")
      (footprint "eagle-import:R0603")
      (libsource (lib "eagle-import") (part "resistor_348_R-EU_R0603"))
    )
    (comp (ref "R8")
      (value "10k")
      (footprint "eagle-import:R0603")
      (libsource (lib "eagle-import") (part "resistor_348_R-EU_R0603"))
    )
    (comp (ref "R9")
      (value "10k")
      (footprint "eagle-import:R0603")
      (libsource (lib "eagle-import") (part "resistor_348_R-EU_R0603"))
    )
    (comp (ref "R10")
      (value "0.22R 3212")
      (footprint "eagle-import:R1210")
      (libsource (lib "eagle-import") (part "resistor_348_R-EU_R1210"))
    )
    (comp (ref "R11")
      (value "0.22R 3212")
      (footprint "eagle-import:R1210")
      (libsource (lib "eagle-import") (part "resistor_348_R-EU_R1210"))
    )
    (comp (ref "R12")
      (value "6K8")
      (footprint "eagle-import:R0603")
      (libsource (lib "eagle-import") (part "resistor_348_R-EU_R0603"))
    )
    (comp (ref "R13")
      (value "10k")
      (footprint "eagle-import:R0603")
      (libsource (lib "eagle-import") (part "resistor_348_R-EU_R0603"))
    )
    (comp (ref "R14")
      (value "10k")
      (footprint "eagle-import:R0603")
      (libsource (lib "eagle-import") (part "resistor_348_R-EU_R0603"))
    )
    (comp (ref "R15")
      (value "10k")
      (footprint "eagle-import:R0603")
      (libsource (lib "eagle-import") (part "resistor_348_R-EU_R0603"))
    )
    (comp (ref "R16")
      (value "10k")
      (footprint "eagle-import:R0603")
      (libsource (lib "eagle-import") (part "resistor_348_R-EU_R0603"))
    )
    (comp (ref "R17")
      (value "3K6")
      (footprint "eagle-import:R0603")
      (libsource (lib "eagle-import") (part "resistor_348_R-EU_R0603"))
    )
    (comp (ref "R18")
      (value "5K1")
      (footprint "eagle-import:R0603")
      (libsource (lib "eagle-import") (part "resistor_348_R-EU_R0603"))
    )
    (comp (ref "R19")
      (value "5K1")
      (footprint "eagle-import:R0603")
      (libsource (lib "eagle-import") (part "resistor_348_R-EU_R0603"))
    )
    (comp (ref "R20")
      (value "10K")
      (footprint "eagle-import:B25P")
      (libsource (lib "eagle-import") (part "TRIM_EU-B25P"))
    )
    (comp (ref "R21")
      (value "10K")
      (footprint "eagle-import:B25P")
      (libsource (lib "eagle-import") (part "TRIM_EU-B25P"))
    )
    (comp (ref "R22")
      (value "5K1")
      (footprint "eagle-import:R0603")
      (libsource (lib "eagle-import") (part "resistor_348_R-EU_R0603"))
    )
    (comp (ref "R23")
      (value "5K1")
      (footprint "eagle-import:R0603")
      (libsource (lib "eagle-import") (part "resistor_348_R-EU_R0603"))
    )
    (comp (ref "R24")
      (value "10r")
      (footprint "eagle-import:R0603")
      (libsource (lib "eagle-import") (part "resistor_R-EU_R0603"))
    )
    (comp (ref "R25")
      (value "100k")
      (footprint "eagle-import:R0603")
      (libsource (lib "eagle-import") (part "resistor_R-EU_R0603"))
    )
    (comp (ref "R26")
      (value "4k7")
      (footprint "eagle-import:R0603")
      (libsource (lib "eagle-import") (part "resistor_R-US_R0603"))
    )
    (comp (ref "R27")
      (value "4k7")
      (footprint "eagle-import:R0603")
      (libsource (lib "eagle-import") (part "resistor_R-US_R0603"))
    )
    (comp (ref "R28")
      (value "10R")
      (footprint "eagle-import:R0603@1")
      (libsource (lib "eagle-import") (part "R-US_R0603"))
    )
    (comp (ref "R29")
      (value "10k")
      (footprint "eagle-import:R0603")
      (libsource (lib "eagle-import") (part "resistor_348_R-EU_R0603"))
    )
    (comp (ref "R30")
      (value "0.22R 3212")
      (footprint "eagle-import:R1210")
      (libsource (lib "eagle-import") (part "resistor_348_R-EU_R1210"))
    )
    (comp (ref "R31")
      (value "0.22R 3212")
      (footprint "eagle-import:R1210")
      (libsource (lib "eagle-import") (part "resistor_348_R-EU_R1210"))
    )
    (comp (ref "R32")
      (value "6K8")
      (footprint "eagle-import:R0603")
      (libsource (lib "eagle-import") (part "resistor_348_R-EU_R0603"))
    )
    (comp (ref "R33")
      (value "10k")
      (footprint "eagle-import:R0603")
      (libsource (lib "eagle-import") (part "resistor_348_R-EU_R0603"))
    )
    (comp (ref "R34")
      (value "10k")
      (footprint "eagle-import:R0603")
      (libsource (lib "eagle-import") (part "resistor_348_R-EU_R0603"))
    )
    (comp (ref "R35")
      (value "10R")
      (footprint "eagle-import:R0603@1")
      (libsource (lib "eagle-import") (part "R-US_R0603"))
    )
    (comp (ref "R36")
      (value "10k")
      (footprint "eagle-import:R0603")
      (libsource (lib "eagle-import") (part "resistor_348_R-EU_R0603"))
    )
    (comp (ref "R37")
      (value "10k")
      (footprint "eagle-import:R0603")
      (libsource (lib "eagle-import") (part "resistor_348_R-EU_R0603"))
    )
    (comp (ref "R38")
      (value "10k")
      (footprint "eagle-import:R0603")
      (libsource (lib "eagle-import") (part "resistor_348_R-EU_R0603"))
    )
    (comp (ref "R39")
      (value "0.22R 3212")
      (footprint "eagle-import:R1210")
      (libsource (lib "eagle-import") (part "resistor_348_R-EU_R1210"))
    )
    (comp (ref "R40")
      (value "0.22R 3212")
      (footprint "eagle-import:R1210")
      (libsource (lib "eagle-import") (part "resistor_348_R-EU_R1210"))
    )
    (comp (ref "R41")
      (value "6K8")
      (footprint "eagle-import:R0603")
      (libsource (lib "eagle-import") (part "resistor_348_R-EU_R0603"))
    )
    (comp (ref "R42")
      (value "10k")
      (footprint "eagle-import:R0603")
      (libsource (lib "eagle-import") (part "resistor_348_R-EU_R0603"))
    )
    (comp (ref "R43")
      (value "10k")
      (footprint "eagle-import:R0603")
      (libsource (lib "eagle-import") (part "resistor_348_R-EU_R0603"))
    )
    (comp (ref "R44")
      (value "100k")
      (footprint "eagle-import:R0603")
      (libsource (lib "eagle-import") (part "resistor_348_R-EU_R0603"))
    )
    (comp (ref "R45")
      (value "10k")
      (footprint "eagle-import:R0603")
      (libsource (lib "eagle-import") (part "resistor_348_R-EU_R0603"))
    )
    (comp (ref "R46")
      (value "10k")
      (footprint "eagle-import:R0603")
      (libsource (lib "eagle-import") (part "resistor_348_R-EU_R0603"))
    )
    (comp (ref "R47")
      (value "10k")
      (footprint "eagle-import:R0603")
      (libsource (lib "eagle-import") (part "resistor_348_R-EU_R0603"))
    )
    (comp (ref "R48")
      (value "0.22R 3212")
      (footprint "eagle-import:R1210")
      (libsource (lib "eagle-import") (part "resistor_348_R-EU_R1210"))
    )
    (comp (ref "R49")
      (value "0.22R 3212")
      (footprint "eagle-import:R1210")
      (libsource (lib "eagle-import") (part "resistor_348_R-EU_R1210"))
    )
    (comp (ref "R50")
      (value "6K8")
      (footprint "eagle-import:R0603")
      (libsource (lib "eagle-import") (part "resistor_348_R-EU_R0603"))
    )
    (comp (ref "R51")
      (value "10k")
      (footprint "eagle-import:R0603")
      (libsource (lib "eagle-import") (part "resistor_348_R-EU_R0603"))
    )
    (comp (ref "R52")
      (value "10k")
      (footprint "eagle-import:R0603")
      (libsource (lib "eagle-import") (part "resistor_348_R-EU_R0603"))
    )
    (comp (ref "R53")
      (value "100k")
      (footprint "eagle-import:R0603")
      (libsource (lib "eagle-import") (part "resistor_348_R-EU_R0603"))
    )
    (comp (ref "R54")
      (value "27R")
      (footprint "eagle-import:R0603-ROUND")
      (libsource (lib "eagle-import") (part "R-EU_R0603"))
    )
    (comp (ref "R55")
      (value "1k")
      (footprint "eagle-import:R0603")
      (libsource (lib "eagle-import") (part "rcl_334_R-EU_R0603"))
    )
    (comp (ref "R56")
      (value "330")
      (footprint "eagle-import:0603-RES")
      (libsource (lib "eagle-import") (part "330OHM1/10W1%(0603)"))
    )
    (comp (ref "R57")
      (value "330")
      (footprint "eagle-import:0603-RES")
      (libsource (lib "eagle-import") (part "330OHM1/10W1%(0603)"))
    )
    (comp (ref "R58")
      (value "330")
      (footprint "eagle-import:0603-RES")
      (libsource (lib "eagle-import") (part "330OHM1/10W1%(0603)"))
    )
    (comp (ref "R59")
      (value "330")
      (footprint "eagle-import:0603-RES")
      (libsource (lib "eagle-import") (part "330OHM1/10W1%(0603)"))
    )
    (comp (ref "R60")
      (value "1k")
      (footprint "eagle-import:R0603")
      (libsource (lib "eagle-import") (part "rcl_334_R-EU_R0603"))
    )
    (comp (ref "R61")
      (value "10k")
      (footprint "eagle-import:R0603")
      (libsource (lib "eagle-import") (part "rcl_334_R-EU_R0603"))
    )
    (comp (ref "R62")
      (value "10R")
      (footprint "eagle-import:R0603")
      (libsource (lib "eagle-import") (part "resistor_R-EU_R0603"))
    )
    (comp (ref "R63")
      (value "100k")
      (footprint "eagle-import:R0603")
      (libsource (lib "eagle-import") (part "resistor_R-EU_R0603"))
    )
    (comp (ref "R64")
      (value "10k")
      (footprint "eagle-import:R0603")
      (libsource (lib "eagle-import") (part "rcl_334_R-EU_R0603"))
    )
    (comp (ref "R65")
      (value "10k")
      (footprint "eagle-import:R0603")
      (libsource (lib "eagle-import") (part "rcl_334_R-EU_R0603"))
    )
    (comp (ref "R66")
      (value "10k")
      (footprint "eagle-import:R0603")
      (libsource (lib "eagle-import") (part "rcl_334_R-EU_R0603"))
    )
    (comp (ref "R67")
      (value "10k")
      (footprint "eagle-import:R0603")
      (libsource (lib "eagle-import") (part "rcl_334_R-EU_R0603"))
    )
    (comp (ref "R68")
      (value "1k")
      (footprint "eagle-import:R0603")
      (libsource (lib "eagle-import") (part "rcl_334_R-EU_R0603"))
    )
    (comp (ref "R69")
      (value "1k")
      (footprint "eagle-import:R0603")
      (libsource (lib "eagle-import") (part "rcl_334_R-EU_R0603"))
    )
    (comp (ref "R70")
      (value "5.1k")
      (footprint "eagle-import:0603@1")
      (libsource (lib "eagle-import") (part "5.1KOHM5.1KOHM-0603-1/10W-1%"))
    )
    (comp (ref "R71")
      (value "5.1k")
      (footprint "eagle-import:0603@1")
      (libsource (lib "eagle-import") (part "5.1KOHM5.1KOHM-0603-1/10W-1%"))
    )
    (comp (ref "R72")
      (value "1K")
      (footprint "eagle-import:0603-RES")
      (libsource (lib "eagle-import") (part "RESISTOR0603-RES"))
    )
    (comp (ref "R73")
      (value "1K")
      (footprint "eagle-import:0603-RES")
      (libsource (lib "eagle-import") (part "RESISTOR0603-RES"))
    )
    (comp (ref "R74")
      (value "1K")
      (footprint "eagle-import:R0603")
      (libsource (lib "eagle-import") (part "resistor_R-US_R0603"))
    )
    (comp (ref "R75")
      (value "1K")
      (footprint "eagle-import:R0603")
      (libsource (lib "eagle-import") (part "resistor_R-US_R0603"))
    )
    (comp (ref "R76")
      (value "1K")
      (footprint "eagle-import:R0603")
      (libsource (lib "eagle-import") (part "resistor_R-US_R0603"))
    )
    (comp (ref "R77")
      (value "1K")
      (footprint "eagle-import:R0603")
      (libsource (lib "eagle-import") (part "resistor_R-US_R0603"))
    )
    (comp (ref "R78")
      (value "10K")
      (footprint "eagle-import:R0603")
      (libsource (lib "eagle-import") (part "resistor_R-US_R0603"))
    )
    (comp (ref "R79")
      (value "10K")
      (footprint "eagle-import:R0603")
      (libsource (lib "eagle-import") (part "resistor_R-US_R0603"))
    )
    (comp (ref "R80")
      (value "10K")
      (footprint "eagle-import:R0603")
      (libsource (lib "eagle-import") (part "resistor_R-US_R0603"))
    )
    (comp (ref "R81")
      (value "10K")
      (footprint "eagle-import:R0603")
      (libsource (lib "eagle-import") (part "resistor_R-US_R0603"))
    )
    (comp (ref "RESET")
      (value "TS42")
      (footprint "eagle-import:TS42")
      (libsource (lib "eagle-import") (part "TS42"))
    )
    (comp (ref "SJ1") (value "SJ") (footprint "eagle-import:SJ") (libsource (lib "eagle-import") (part "SJ")))
    (comp (ref "SJ2") (value "SJ") (footprint "eagle-import:SJ") (libsource (lib "eagle-import") (part "SJ")))
    (comp (ref "SJ3") (value "SJ") (footprint "eagle-import:SJ") (libsource (lib "eagle-import") (part "SJ")))
    (comp (ref "SJ4") (value "SJ") (footprint "eagle-import:SJ") (libsource (lib "eagle-import") (part "SJ")))
    (comp (ref "SJ5") (value "SJ") (footprint "eagle-import:SJ") (libsource (lib "eagle-import") (part "SJ")))
    (comp (ref "SJ6") (value "SJ") (footprint "eagle-import:SJ") (libsource (lib "eagle-import") (part "SJ")))
    (comp (ref "SJ7") (value "SJ") (footprint "eagle-import:SJ") (libsource (lib "eagle-import") (part "SJ")))
    (comp (ref "SJ8") (value "SJ") (footprint "eagle-import:SJ") (libsource (lib "eagle-import") (part "SJ")))
    (comp (ref "T2")
      (value "FDN340P")
      (footprint "eagle-import:SOT-23")
      (libsource (lib "eagle-import") (part "PMOSSOT23"))
    )
    (comp (ref "U$1")
      (value "TB67S109AFNG")
      (footprint "eagle-import:TB67S109AFTG-HTSSPO48-P-300-0.50")
      (libsource (lib "eagle-import") (part "TB67S109AFTG"))
    )
    (comp (ref "U$2")
      (value "TB67S109AFNG")
      (footprint "eagle-import:TB67S109AFTG-HTSSPO48-P-300-0.50")
      (libsource (lib "eagle-import") (part "TB67S109AFTG"))
    )
    (comp (ref "U$4")
      (value "ATQ-FUSE")
      (footprint "eagle-import:ATQ-FUSE")
      (libsource (lib "eagle-import") (part "ATQ-FUSE"))
    )
    (comp (ref "U$7")
      (value "TB67S109AFNG")
      (footprint "eagle-import:TB67S109AFTG-HTSSPO48-P-300-0.50")
      (libsource (lib "eagle-import") (part "TB67S109AFTG"))
    )
    (comp (ref "U$17")
      (value "TB67S109AFNG")
      (footprint "eagle-import:TB67S109AFTG-HTSSPO48-P-300-0.50")
      (libsource (lib "eagle-import") (part "TB67S109AFTG"))
    )
    (comp (ref "U1")
      (value "TLP291-4")
      (footprint "eagle-import:SO16_TOS")
      (fields (field (name "COPYRIGHT") "Copyright (C) 2018 Accelerated Designs. All rights reserved"))
      (libsource (lib "eagle-import") (part "TLP291-4"))
    )
    (comp (ref "U2")
      (value "USD-SOCKETUSD")
      (footprint "eagle-import:USD-SOCKET-PP")
      (libsource (lib "eagle-import") (part "USD-SOCKETUSD"))
    )
    (comp (ref "U6")
      (value "FT232RLSSOP")
      (footprint "eagle-import:SSOP28DB")
      (libsource (lib "eagle-import") (part "FT232RLSSOP"))
    )
    (comp (ref "X-END1")
      (value "Phoenix Pluggable 3.81mm 2 way")
      (footprint "eagle-import:MC1.5_2-G-3.81")
      (libsource (lib "eagle-import") (part "MC1.5/2"))
    )
    (comp (ref "X-END2")
      (value "Phoenix Pluggable 3.81mm 2 way")
      (footprint "eagle-import:MC1.5_2-G-3.81")
      (libsource (lib "eagle-import") (part "MC1.5/2"))
    )
    (comp (ref "X-END3")
      (value "Phoenix Pluggable 3.81mm 2 way")
      (footprint "eagle-import:MC1.5_2-G-3.81")
      (libsource (lib "eagle-import") (part "MC1.5/2"))
    )
    (comp (ref "Z-CONN1")
      (value "CONN_05X2SHD_LOCK")
      (footprint "eagle-import:2X5-SHROUDED_LOCK")
      (libsource (lib "eagle-import") (part "CONN_05X2SHD_LOCK"))
    )
  )
  (nets
    (net (code "1") (name "+3V3") (class "Default")
      (node (ref "C28") (pin "2") (pinfunction "2_2") (pintype "passive"))
      (node (ref "C47") (pin "A") (pinfunction "+_A") (pintype "passive"))
      (node (ref "C49") (pin "1") (pinfunction "1_1") (pintype "passive"))
      (node (ref "C50") (pin "1") (pinfunction "1_1") (pintype "passive"))
      (node (ref "C52") (pin "A") (pinfunction "+_A") (pintype "passive"))
      (node (ref "IC1") (pin "1") (pinfunction "VDD_1") (pintype "power_in"))
      (node (ref "IC2") (pin "4") (pinfunction "OUT_4") (pintype "passive"))
      (node (ref "IC5") (pin "6") (pinfunction "-IN_6") (pintype "input"))
      (node (ref "U2") (pin "4") (pinfunction "VCC_4") (pintype "bidirectional"))
    )
    (net (code "2") (name "3VUSB") (class "Default")
      (node (ref "C45") (pin "1") (pinfunction "1_1") (pintype "passive"))
      (node (ref "U6") (pin "17") (pinfunction "3V3OUT_17") (pintype "output"))
    )
    (net (code "3") (name "5-GND") (class "Default")
      (node (ref "RESET") (pin "5") (pinfunction "5-GND_5") (pintype "power_in"))
    )
    (net (code "4") (name "5VREG") (class "Default")
      (node (ref "C15") (pin "1") (pinfunction "1_1") (pintype "passive"))
      (node (ref "C20") (pin "1") (pinfunction "1_1") (pintype "passive"))
      (node (ref "C25") (pin "1") (pinfunction "1_1") (pintype "passive"))
      (node (ref "C30") (pin "2") (pinfunction "2_2") (pintype "passive"))
      (node (ref "C51") (pin "A") (pinfunction "+_A") (pintype "passive"))
      (node (ref "C56") (pin "+") (pinfunction "+_+") (pintype "passive"))
      (node (ref "C6") (pin "1") (pinfunction "1_1") (pintype "passive"))
      (node (ref "C7") (pin "1") (pinfunction "1_1") (pintype "passive"))
      (node (ref "C8") (pin "1") (pinfunction "1_1") (pintype "passive"))
      (node (ref "C9") (pin "1") (pinfunction "1_1") (pintype "passive"))
      (node (ref "IC2") (pin "3") (pinfunction "IN_3") (pintype "input"))
      (node (ref "IC3") (pin "10") (pinfunction "VCC_10") (pintype "power_in"))
      (node (ref "IC3") (pin "100") (pinfunction "AVCC_100") (pintype "power_in"))
      (node (ref "IC3") (pin "31") (pinfunction "VCC1_31") (pintype "power_in"))
      (node (ref "IC3") (pin "61") (pinfunction "VCC2_61") (pintype "power_in"))
      (node (ref "IC3") (pin "80") (pinfunction "VCC3_80") (pintype "power_in"))
      (node (ref "IC5") (pin "8") (pinfunction "V+_8") (pintype "power_in"))
      (node (ref "IC9") (pin "3") (pinfunction "FB_3") (pintype "bidirectional"))
      (node (ref "ICSP") (pin "2") (pinfunction "2_2") (pintype "passive"))
      (node (ref "L1") (pin "2") (pinfunction "2_2") (pintype "passive"))
      (node (ref "L2") (pin "1") (pinfunction "1_1") (pintype "passive"))
      (node (ref "LED1") (pin "C") (pinfunction "C_C") (pintype "passive"))
      (node (ref "LED2") (pin "C") (pinfunction "C_C") (pintype "passive"))
      (node (ref "LED3") (pin "C") (pinfunction "C_C") (pintype "passive"))
      (node (ref "LED4") (pin "C") (pinfunction "C_C") (pintype "passive"))
      (node (ref "R12") (pin "2") (pinfunction "2_2") (pintype "passive"))
      (node (ref "R13") (pin "2") (pinfunction "2_2") (pintype "passive"))
      (node (ref "R14") (pin "2") (pinfunction "2_2") (pintype "passive"))
      (node (ref "R15") (pin "2") (pinfunction "2_2") (pintype "passive"))
      (node (ref "R16") (pin "2") (pinfunction "2_2") (pintype "passive"))
      (node (ref "R18") (pin "2") (pinfunction "2_2") (pintype "passive"))
      (node (ref "R19") (pin "2") (pinfunction "2_2") (pintype "passive"))
      (node (ref "R22") (pin "2") (pinfunction "2_2") (pintype "passive"))
      (node (ref "R23") (pin "2") (pinfunction "2_2") (pintype "passive"))
      (node (ref "R29") (pin "2") (pinfunction "2_2") (pintype "passive"))
      (node (ref "R32") (pin "2") (pinfunction "2_2") (pintype "passive"))
      (node (ref "R33") (pin "2") (pinfunction "2_2") (pintype "passive"))
      (node (ref "R34") (pin "2") (pinfunction "2_2") (pintype "passive"))
      (node (ref "R36") (pin "2") (pinfunction "2_2") (pintype "passive"))
      (node (ref "R37") (pin "2") (pinfunction "2_2") (pintype "passive"))
      (node (ref "R38") (pin "2") (pinfunction "2_2") (pintype "passive"))
      (node (ref "R41") (pin "2") (pinfunction "2_2") (pintype "passive"))
      (node (ref "R42") (pin "2") (pinfunction "2_2") (pintype "passive"))
      (node (ref "R43") (pin "2") (pinfunction "2_2") (pintype "passive"))
      (node (ref "R45") (pin "2") (pinfunction "2_2") (pintype "passive"))
      (node (ref "R46") (pin "2") (pinfunction "2_2") (pintype "passive"))
      (node (ref "R47") (pin "2") (pinfunction "2_2") (pintype "passive"))
      (node (ref "R50") (pin "2") (pinfunction "2_2") (pintype "passive"))
      (node (ref "R51") (pin "2") (pinfunction "2_2") (pintype "passive"))
      (node (ref "R52") (pin "2") (pinfunction "2_2") (pintype "passive"))
      (node (ref "R6") (pin "2") (pinfunction "2_2") (pintype "passive"))
      (node (ref "R60") (pin "1") (pinfunction "1_1") (pintype "passive"))
      (node (ref "R61") (pin "2") (pinfunction "2_2") (pintype "passive"))
      (node (ref "R64") (pin "2") (pinfunction "2_2") (pintype "passive"))
      (node (ref "R65") (pin "2") (pinfunction "2_2") (pintype "passive"))
      (node (ref "R74") (pin "1") (pinfunction "1_1") (pintype "passive"))
      (node (ref "R75") (pin "1") (pinfunction "1_1") (pintype "passive"))
      (node (ref "R76") (pin "1") (pinfunction "1_1") (pintype "passive"))
      (node (ref "R77") (pin "1") (pinfunction "1_1") (pintype "passive"))
      (node (ref "R78") (pin "2") (pinfunction "2_2") (pintype "passive"))
      (node (ref "R79") (pin "2") (pinfunction "2_2") (pintype "passive"))
      (node (ref "R8") (pin "2") (pinfunction "2_2") (pintype "passive"))
      (node (ref "R80") (pin "2") (pinfunction "2_2") (pintype "passive"))
      (node (ref "R81") (pin "2") (pinfunction "2_2") (pintype "passive"))
      (node (ref "R9") (pin "2") (pinfunction "2_2") (pintype "passive"))
      (node (ref "T2") (pin "2") (pinfunction "S_2") (pintype "passive"))
    )
    (net (code "5") (name "AGND") (class "Default")
      (node (ref "BEDTH") (pin "1") (pinfunction "1_1") (pintype "passive"))
      (node (ref "C3") (pin "C") (pinfunction "-_C") (pintype "passive"))
      (node (ref "C4") (pin "C") (pinfunction "-_C") (pintype "passive"))
      (node (ref "ETHERM") (pin "1") (pinfunction "1_1") (pintype "passive"))
      (node (ref "J1") (pin "9") (pinfunction "9_9") (pintype "passive"))
      (node (ref "L3") (pin "1") (pinfunction "1_1") (pintype "passive"))
    )
    (net (code "6") (name "AREF") (class "Default")
      (node (ref "C5") (pin "1") (pinfunction "1_1") (pintype "passive"))
      (node (ref "IC3") (pin "98") (pinfunction "AREF_98") (pintype "bidirectional"))
    )
    (net (code "7") (name "AVCC") (class "Default")
      (node (ref "L1") (pin "1") (pinfunction "1_1") (pintype "passive"))
      (node (ref "R26") (pin "1") (pinfunction "1_1") (pintype "passive"))
      (node (ref "R27") (pin "1") (pinfunction "1_1") (pintype "passive"))
    )
    (net (code "8") (name "BED-NEG1") (class "Default")
      (node (ref "BED") (pin "1") (pinfunction "1_1") (pintype "passive"))
      (node (ref "D2") (pin "A") (pinfunction "A_A") (pintype "passive"))
      (node (ref "MOS2") (pin "2") (pinfunction "D_2") (pintype "passive"))
    )
    (net (code "9") (name "CMP") (class "Default")
      (node (ref "C29") (pin "2") (pinfunction "2_2") (pintype "passive"))
      (node (ref "IC5") (pin "5") (pinfunction "+IN_5") (pintype "input"))
      (node (ref "R66") (pin "1") (pinfunction "1_1") (pintype "passive"))
      (node (ref "R67") (pin "2") (pinfunction "2_2") (pintype "passive"))
    )
    (net (code "10") (name "CS") (class "Default")
      (node (ref "IC1") (pin "2") (pinfunction "O_2") (pintype "output"))
      (node (ref "U2") (pin "2") (pinfunction "CS_2") (pintype "bidirectional"))
    )
    (net (code "11") (name "CTS") (class "Default")
      (node (ref "U6") (pin "11") (pinfunction "CTS_11") (pintype "input"))
    )
    (net (code "12") (name "D+1") (class "Default")
      (node (ref "J3") (pin "A6") (pinfunction "D+_A6") (pintype "bidirectional"))
      (node (ref "J3") (pin "B6") (pinfunction "D+_B6") (pintype "bidirectional"))
      (node (ref "U6") (pin "15") (pinfunction "USBDP_15") (pintype "bidirectional"))
    )
    (net (code "13") (name "D-1") (class "Default")
      (node (ref "J3") (pin "A7") (pinfunction "D-_A7") (pintype "bidirectional"))
      (node (ref "J3") (pin "B7") (pinfunction "D-_B7") (pintype "bidirectional"))
      (node (ref "U6") (pin "16") (pinfunction "USBDM_16") (pintype "bidirectional"))
    )
    (net (code "14") (name "D0") (class "Default")
      (node (ref "IC3") (pin "2") (pinfunction "(RXD0/PCIN8)PE0_2") (pintype "bidirectional"))
      (node (ref "R68") (pin "2") (pinfunction "2_2") (pintype "passive"))
    )
    (net (code "15") (name "D1") (class "Default")
      (node (ref "IC3") (pin "3") (pinfunction "(TXD0)PE1_3") (pintype "bidirectional"))
      (node (ref "R69") (pin "2") (pinfunction "2_2") (pintype "passive"))
    )
    (net (code "16") (name "D2{slash}EENABLE") (class "Default")
      (node (ref "IC3") (pin "6") (pinfunction "(OC3B/INT4)PE4_6") (pintype "bidirectional"))
      (node (ref "U$7") (pin "ENABLE") (pinfunction "ENABLE_ENABLE") (pintype "bidirectional"))
    )
    (net (code "17") (name "D3") (class "Default")
      (node (ref "IC3") (pin "7") (pinfunction "(OC3C/INT5)PE5_7") (pintype "bidirectional"))
      (node (ref "R78") (pin "1") (pinfunction "1_1") (pintype "passive"))
      (node (ref "U1") (pin "16") (pinfunction "16_16") (pintype "passive"))
    )
    (net (code "18") (name "D4{slash}EDIR") (class "Default")
      (node (ref "IC3") (pin "1") (pinfunction "(OC0B)PG5_1") (pintype "bidirectional"))
      (node (ref "U$7") (pin "CS/CCW") (pinfunction "CW/CCW_CS/CCW") (pintype "bidirectional"))
    )
    (net (code "19") (name "D5{slash}ESTEP") (class "Default")
      (node (ref "IC3") (pin "5") (pinfunction "(OC3A/AIN1)PE3_5") (pintype "bidirectional"))
      (node (ref "U$7") (pin "CLK") (pinfunction "CLK_CLK") (pintype "bidirectional"))
    )
    (net (code "20") (name "D6") (class "Default")
      (node (ref "IC3") (pin "8") (pinfunction "(T3/INT6)PE6_8") (pintype "bidirectional"))
    )
    (net (code "21") (name "D7") (class "Default")
      (node (ref "IC3") (pin "9") (pinfunction "(CLKO/ICP3/INT7)PE7_9") (pintype "bidirectional"))
    )
    (net (code "22") (name "D8") (class "Default")
      (node (ref "IC3") (pin "17") (pinfunction "PH5(OC4C)_17") (pintype "bidirectional"))
      (node (ref "R79") (pin "1") (pinfunction "1_1") (pintype "passive"))
      (node (ref "U1") (pin "14") (pinfunction "14_14") (pintype "passive"))
    )
    (net (code "23") (name "D9") (class "Default")
      (node (ref "IC3") (pin "18") (pinfunction "PH6(OC2B)_18") (pintype "bidirectional"))
      (node (ref "R80") (pin "1") (pinfunction "1_1") (pintype "passive"))
      (node (ref "U1") (pin "12") (pinfunction "12_12") (pintype "passive"))
    )
    (net (code "24") (name "D10") (class "Default")
      (node (ref "IC3") (pin "23") (pinfunction "(OC2A/PCINT4)PB4_23") (pintype "bidirectional"))
      (node (ref "R81") (pin "1") (pinfunction "1_1") (pintype "passive"))
      (node (ref "U1") (pin "10") (pinfunction "10_10") (pintype "passive"))
    )
    (net (code "25") (name "D11") (class "Default")
      (node (ref "IC3") (pin "24") (pinfunction "(OC1A/PCINT5)PB5_24") (pintype "bidirectional"))
    )
    (net (code "26") (name "D12") (class "Default")
      (node (ref "IC3") (pin "25") (pinfunction "(OC1B/PCINT6)PB6_25") (pintype "bidirectional"))
    )
    (net (code "27") (name "D13") (class "Default")
      (node (ref "IC3") (pin "26") (pinfunction "(OC0A/OC1C/PCINT7)PB7_26") (pintype "bidirectional"))
      (node (ref "R55") (pin "1") (pinfunction "1_1") (pintype "passive"))
    )
    (net (code "28") (name "D14{slash}TXD3") (class "Default")
      (node (ref "IC3") (pin "64") (pinfunction "PJ1(TXD3/PCINT10)_64") (pintype "bidirectional"))
    )
    (net (code "29") (name "D15{slash}RXD3") (class "Default")
      (node (ref "IC3") (pin "63") (pinfunction "PJ0(RXD3/PCINT9)_63") (pintype "bidirectional"))
    )
    (net (code "30") (name "D16{slash}TXD2") (class "Default")
      (node (ref "IC3") (pin "13") (pinfunction "PH1(TXD2)_13") (pintype "bidirectional"))
    )
    (net (code "31") (name "D17{slash}RXD2") (class "Default")
      (node (ref "IC3") (pin "12") (pinfunction "PH0(RXD2)_12") (pintype "bidirectional"))
    )
    (net (code "32") (name "D18{slash}TXD1") (class "Default")
      (node (ref "IC3") (pin "46") (pinfunction "(TXD1/INT3)PD3_46") (pintype "bidirectional"))
    )
    (net (code "33") (name "D19{slash}RXD1") (class "Default")
      (node (ref "IC3") (pin "45") (pinfunction "(RXD1/INT2)PD2_45") (pintype "bidirectional"))
    )
    (net (code "34") (name "D20{slash}SDA") (class "Default")
      (node (ref "IC3") (pin "44") (pinfunction "(SDA/INT1)PD1_44") (pintype "bidirectional"))
      (node (ref "R65") (pin "1") (pinfunction "1_1") (pintype "passive"))
    )
    (net (code "35") (name "D21{slash}SCL") (class "Default")
      (node (ref "IC3") (pin "43") (pinfunction "(SCL/INT0)PD0_43") (pintype "bidirectional"))
      (node (ref "R64") (pin "1") (pinfunction "1_1") (pintype "passive"))
    )
    (net (code "36") (name "D22") (class "Default")
      (node (ref "IC3") (pin "78") (pinfunction "(AD0)PA0_78") (pintype "bidirectional"))
    )
    (net (code "37") (name "D23") (class "Default")
      (node (ref "IC3") (pin "77") (pinfunction "(AD1)PA1_77") (pintype "bidirectional"))
    )
    (net (code "38") (name "D24") (class "Default")
      (node (ref "IC3") (pin "76") (pinfunction "(AD2)PA2_76") (pintype "bidirectional"))
    )
    (net (code "39") (name "D25") (class "Default")
      (node (ref "IC3") (pin "75") (pinfunction "(AD3)PA3_75") (pintype "bidirectional"))
    )
    (net (code "40") (name "D26") (class "Default")
      (node (ref "IC3") (pin "74") (pinfunction "(AD4)PA4_74") (pintype "bidirectional"))
    )
    (net (code "41") (name "D27") (class "Default")
      (node (ref "IC3") (pin "73") (pinfunction "(AD5)PA5_73") (pintype "bidirectional"))
    )
    (net (code "42") (name "D28") (class "Default")
      (node (ref "IC3") (pin "72") (pinfunction "(AD6)PA6_72") (pintype "bidirectional"))
    )
    (net (code "43") (name "D29") (class "Default")
      (node (ref "IC3") (pin "71") (pinfunction "(AD7)PA7_71") (pintype "bidirectional"))
    )
    (net (code "44") (name "D30") (class "Default")
      (node (ref "IC3") (pin "60") (pinfunction "(A15)PC7_60") (pintype "bidirectional"))
    )
    (net (code "45") (name "D31") (class "Default")
      (node (ref "IC3") (pin "59") (pinfunction "(A14)PC6_59") (pintype "bidirectional"))
    )
    (net (code "46") (name "D32") (class "Default")
      (node (ref "IC3") (pin "58") (pinfunction "(A13)PC5_58") (pintype "bidirectional"))
    )
    (net (code "47") (name "D33") (class "Default")
      (node (ref "IC3") (pin "57") (pinfunction "(A12)PC4_57") (pintype "bidirectional"))
    )
    (net (code "48") (name "D34") (class "Default")
      (node (ref "IC3") (pin "56") (pinfunction "(A11)PC3_56") (pintype "bidirectional"))
    )
    (net (code "49") (name "D35") (class "Default")
      (node (ref "IC3") (pin "55") (pinfunction "(A10)PC2_55") (pintype "bidirectional"))
    )
    (net (code "50") (name "D36") (class "Default")
      (node (ref "IC3") (pin "54") (pinfunction "(A9)PC1_54") (pintype "bidirectional"))
    )
    (net (code "51") (name "D37") (class "Default")
      (node (ref "IC3") (pin "53") (pinfunction "(A8)PC0_53") (pintype "bidirectional"))
    )
    (net (code "52") (name "D38") (class "Default")
      (node (ref "IC3") (pin "50") (pinfunction "(T0)PD7_50") (pintype "bidirectional"))
    )
    (net (code "53") (name "D39") (class "Default")
      (node (ref "IC3") (pin "70") (pinfunction "(ALE)PG2_70") (pintype "bidirectional"))
    )
    (net (code "54") (name "D40") (class "Default")
      (node (ref "IC3") (pin "52") (pinfunction "(RD)PG1_52") (pintype "bidirectional"))
    )
    (net (code "55") (name "D41") (class "Default")
      (node (ref "IC3") (pin "51") (pinfunction "(WR)PG0_51") (pintype "bidirectional"))
    )
    (net (code "56") (name "D42") (class "Default")
      (node (ref "IC3") (pin "42") (pinfunction "PL7_42") (pintype "bidirectional"))
    )
    (net (code "57") (name "D43") (class "Default")
      (node (ref "IC3") (pin "41") (pinfunction "PL6_41") (pintype "bidirectional"))
    )
    (net (code "58") (name "D44") (class "Default")
      (node (ref "IC3") (pin "40") (pinfunction "PL5(OC5C)_40") (pintype "bidirectional"))
    )
    (net (code "59") (name "D45") (class "Default")
      (node (ref "IC3") (pin "39") (pinfunction "PL4(OC5B)_39") (pintype "bidirectional"))
    )
    (net (code "60") (name "D46") (class "Default")
      (node (ref "IC3") (pin "38") (pinfunction "PL3(OC5A)_38") (pintype "bidirectional"))
    )
    (net (code "61") (name "D47") (class "Default")
      (node (ref "IC3") (pin "37") (pinfunction "PL2(T5)_37") (pintype "bidirectional"))
    )
    (net (code "62") (name "D48") (class "Default")
      (node (ref "IC3") (pin "36") (pinfunction "PL1(ICP5)_36") (pintype "bidirectional"))
    )
    (net (code "63") (name "D49") (class "Default")
      (node (ref "IC3") (pin "35") (pinfunction "PL0(ICP4)_35") (pintype "bidirectional"))
    )
    (net (code "64") (name "D50{slash}MISO") (class "Default")
      (node (ref "IC3") (pin "22") (pinfunction "(MISO/PCINT3)PB3_22") (pintype "bidirectional"))
      (node (ref "ICSP") (pin "1") (pinfunction "1_1") (pintype "passive"))
      (node (ref "U2") (pin "7") (pinfunction "DO_7") (pintype "bidirectional"))
    )
    (net (code "65") (name "D51{slash}MOSI") (class "Default")
      (node (ref "IC1") (pin "5") (pinfunction "I_5") (pintype "input"))
      (node (ref "IC3") (pin "21") (pinfunction "(MOSI/PCINT2)PB2_21") (pintype "bidirectional"))
      (node (ref "ICSP") (pin "4") (pinfunction "4_4") (pintype "passive"))
    )
    (net (code "66") (name "D52{slash}SCK") (class "Default")
      (node (ref "IC1") (pin "7") (pinfunction "I_7") (pintype "input"))
      (node (ref "IC3") (pin "20") (pinfunction "(SCK/PCINT1)PB1_20") (pintype "bidirectional"))
      (node (ref "ICSP") (pin "3") (pinfunction "3_3") (pintype "passive"))
    )
    (net (code "67") (name "D53{slash}SS") (class "Default")
      (node (ref "IC1") (pin "3") (pinfunction "I_3") (pintype "input"))
      (node (ref "IC3") (pin "19") (pinfunction "(SS/PCINT0)PB0_19") (pintype "bidirectional"))
    )
    (net (code "68") (name "D54{slash}ADC0") (class "Default")
      (node (ref "IC3") (pin "97") (pinfunction "(ADC0)PF0_97") (pintype "bidirectional"))
    )
    (net (code "69") (name "D55{slash}ADC1{slash}ZENABLE") (class "Default")
      (node (ref "IC3") (pin "96") (pinfunction "(ADC1)PF1_96") (pintype "bidirectional"))
      (node (ref "U$2") (pin "ENABLE") (pinfunction "ENABLE_ENABLE") (pintype "bidirectional"))
    )
    (net (code "70") (name "D56{slash}ADC2{slash}ZSTEP") (class "Default")
      (node (ref "IC3") (pin "95") (pinfunction "(ADC2)PF2_95") (pintype "bidirectional"))
      (node (ref "U$2") (pin "CLK") (pinfunction "CLK_CLK") (pintype "bidirectional"))
    )
    (net (code "71") (name "D57{slash}ADC3{slash}ZDIR") (class "Default")
      (node (ref "IC3") (pin "94") (pinfunction "(ADC3)PF3_94") (pintype "bidirectional"))
      (node (ref "U$2") (pin "CS/CCW") (pinfunction "CW/CCW_CS/CCW") (pintype "bidirectional"))
    )
    (net (code "72") (name "D58{slash}ADC4{slash}YENABLE") (class "Default")
      (node (ref "IC3") (pin "93") (pinfunction "(ADC4/TCK)PF4_93") (pintype "bidirectional"))
      (node (ref "U$1") (pin "ENABLE") (pinfunction "ENABLE_ENABLE") (pintype "bidirectional"))
    )
    (net (code "73") (name "D59{slash}ADC5{slash}YSTEP") (class "Default")
      (node (ref "IC3") (pin "92") (pinfunction "(ADC5/TMS)PF5_92") (pintype "bidirectional"))
      (node (ref "U$1") (pin "CLK") (pinfunction "CLK_CLK") (pintype "bidirectional"))
    )
    (net (code "74") (name "D60{slash}ADC6{slash}YDIR") (class "Default")
      (node (ref "IC3") (pin "91") (pinfunction "(ADC6/TDO)PF6_91") (pintype "bidirectional"))
      (node (ref "U$1") (pin "CS/CCW") (pinfunction "CW/CCW_CS/CCW") (pintype "bidirectional"))
    )
    (net (code "75") (name "D61{slash}ADC7{slash}XENABLE") (class "Default")
      (node (ref "IC3") (pin "90") (pinfunction "(ADC7/TDI)PF7_90") (pintype "bidirectional"))
      (node (ref "U$17") (pin "ENABLE") (pinfunction "ENABLE_ENABLE") (pintype "bidirectional"))
    )
    (net (code "76") (name "D62{slash}ADC8{slash}XSTEP") (class "Default")
      (node (ref "IC3") (pin "89") (pinfunction "PK0(ADC8/PCINT16)_89") (pintype "bidirectional"))
      (node (ref "U$17") (pin "CLK") (pinfunction "CLK_CLK") (pintype "bidirectional"))
    )
    (net (code "77") (name "D63{slash}ADC9{slash}XDIR") (class "Default")
      (node (ref "IC3") (pin "88") (pinfunction "PK1(ADC9/PCINT17)_88") (pintype "bidirectional"))
      (node (ref "U$17") (pin "CS/CCW") (pinfunction "CW/CCW_CS/CCW") (pintype "bidirectional"))
    )
    (net (code "78") (name "D64{slash}ADC10{slash}BED") (class "Default")
      (node (ref "IC3") (pin "87") (pinfunction "PK2(ADC10/PCINT18)_87") (pintype "bidirectional"))
      (node (ref "R24") (pin "1") (pinfunction "1_1") (pintype "passive"))
    )
    (net (code "79") (name "D65{slash}ADC11{slash}HOTEND") (class "Default")
      (node (ref "IC3") (pin "86") (pinfunction "PK3(ADC11/PCINT19)_86") (pintype "bidirectional"))
      (node (ref "R62") (pin "1") (pinfunction "1_1") (pintype "passive"))
    )
    (net (code "80") (name "D66{slash}ADC12{slash}E-FAN") (class "Default")
      (node (ref "IC3") (pin "85") (pinfunction "PK4(ADC12/PCINT20)_85") (pintype "bidirectional"))
      (node (ref "R35") (pin "2") (pinfunction "2_2") (pintype "passive"))
    )
    (net (code "81") (name "D67{slash}ADC13") (class "Default")
      (node (ref "IC3") (pin "84") (pinfunction "PK5(ADC13/PCINT21)_84") (pintype "bidirectional"))
      (node (ref "R28") (pin "2") (pinfunction "2_2") (pintype "passive"))
    )
    (net (code "82") (name "D68{slash}ADC14{slash}TH2_BED") (class "Default")
      (node (ref "BEDTH") (pin "2") (pinfunction "1_2") (pintype "passive"))
      (node (ref "C4") (pin "A") (pinfunction "+_A") (pintype "passive"))
      (node (ref "IC3") (pin "83") (pinfunction "PK6(ADC14/PCINT22)_83") (pintype "bidirectional"))
      (node (ref "R27") (pin "2") (pinfunction "2_2") (pintype "passive"))
    )
    (net (code "83") (name "D69{slash}ADC15{slash}TH1_HOTEND") (class "Default")
      (node (ref "C3") (pin "A") (pinfunction "+_A") (pintype "passive"))
      (node (ref "ETHERM") (pin "2") (pinfunction "1_2") (pintype "passive"))
      (node (ref "IC3") (pin "82") (pinfunction "PK7(ADC15/PCINT23)_82") (pintype "bidirectional"))
      (node (ref "J1") (pin "10") (pinfunction "10_10") (pintype "passive"))
      (node (ref "R26") (pin "2") (pinfunction "2_2") (pintype "passive"))
    )
    (net (code "84") (name "DI") (class "Default")
      (node (ref "IC1") (pin "4") (pinfunction "O_4") (pintype "output"))
      (node (ref "U2") (pin "3") (pinfunction "DI_3") (pintype "bidirectional"))
    )
    (net (code "85") (name "DTR") (class "Default")
      (node (ref "C46") (pin "1") (pinfunction "1_1") (pintype "passive"))
      (node (ref "U6") (pin "2") (pinfunction "DTR_2") (pintype "output"))
    )
    (net (code "86") (name "E-FAN-NEG") (class "Default")
      (node (ref "D13") (pin "A") (pinfunction "A_A") (pintype "passive"))
      (node (ref "J2") (pin "1") (pinfunction "1_1") (pintype "passive"))
      (node (ref "J2") (pin "2") (pinfunction "2_2") (pintype "passive"))
      (node (ref "Q1") (pin "4") (pinfunction "D_4") (pintype "passive"))
      (node (ref "X-END3") (pin "1") (pinfunction "1_1") (pintype "passive"))
    )
    (net (code "87") (name "EMODE0") (class "Default")
      (node (ref "R45") (pin "1") (pinfunction "1_1") (pintype "passive"))
      (node (ref "U$7") (pin "DMODE0") (pinfunction "DMODE0_DMODE0") (pintype "bidirectional"))
    )
    (net (code "88") (name "EMODE1") (class "Default")
      (node (ref "R46") (pin "1") (pinfunction "1_1") (pintype "passive"))
      (node (ref "SJ5") (pin "2") (pinfunction "2_2") (pintype "passive"))
      (node (ref "U$7") (pin "DMODE1") (pinfunction "DMODE1_DMODE1") (pintype "bidirectional"))
    )
    (net (code "89") (name "EMODE2") (class "Default")
      (node (ref "R47") (pin "1") (pinfunction "1_1") (pintype "passive"))
      (node (ref "SJ6") (pin "2") (pinfunction "2_2") (pintype "passive"))
      (node (ref "U$7") (pin "DMODE2") (pinfunction "DMODE2_DMODE2") (pintype "bidirectional"))
    )
    (net (code "90") (name "EOUT-A+") (class "Default")
      (node (ref "D9") (pin "C") (pinfunction "C_C") (pintype "passive"))
      (node (ref "J7") (pin "1") (pinfunction "1_1") (pintype "passive"))
      (node (ref "J7") (pin "2") (pinfunction "2_2") (pintype "passive"))
      (node (ref "U$7") (pin "OUTA+1") (pinfunction "OUTA+1_OUTA+1") (pintype "bidirectional"))
      (node (ref "U$7") (pin "OUTA+2") (pinfunction "OUTA+2_OUTA+2") (pintype "bidirectional"))
    )
    (net (code "91") (name "EOUT-A-") (class "Default")
      (node (ref "D9") (pin "A") (pinfunction "A_A") (pintype "passive"))
      (node (ref "J7") (pin "3") (pinfunction "3_3") (pintype "passive"))
      (node (ref "J7") (pin "4") (pinfunction "4_4") (pintype "passive"))
      (node (ref "U$7") (pin "OUTA-1") (pinfunction "OUTA-1_OUTA-1") (pintype "bidirectional"))
      (node (ref "U$7") (pin "OUTA-2") (pinfunction "OUTA-2_OUTA-2") (pintype "bidirectional"))
    )
    (net (code "92") (name "EOUT-B+") (class "Default")
      (node (ref "D10") (pin "A") (pinfunction "A_A") (pintype "passive"))
      (node (ref "J7") (pin "7") (pinfunction "7_7") (pintype "passive"))
      (node (ref "J7") (pin "8") (pinfunction "8_8") (pintype "passive"))
      (node (ref "U$7") (pin "OUTB+1") (pinfunction "OUTB+1_OUTB+1") (pintype "bidirectional"))
      (node (ref "U$7") (pin "OUTB+2") (pinfunction "OUTB+2_OUTB+2") (pintype "bidirectional"))
    )
    (net (code "93") (name "EOUT-B-") (class "Default")
      (node (ref "D10") (pin "C") (pinfunction "C_C") (pintype "passive"))
      (node (ref "J7") (pin "5") (pinfunction "5_5") (pintype "passive"))
      (node (ref "J7") (pin "6") (pinfunction "6_6") (pintype "passive"))
      (node (ref "U$7") (pin "OUTB-1") (pinfunction "OUTB-1_OUTB-1") (pintype "bidirectional"))
      (node (ref "U$7") (pin "OUTB-2") (pinfunction "OUTB-2_OUTB-2") (pintype "bidirectional"))
    )
    (net (code "94") (name "GATE_CMD") (class "Default")
      (node (ref "IC5") (pin "7") (pinfunction "OUT_7") (pintype "output"))
      (node (ref "T2") (pin "3") (pinfunction "G_3") (pintype "passive"))
    )
    (net (code "95") (name "GND") (class "Default")
      (node (ref "C1") (pin "-") (pinfunction "-_-") (pintype "passive"))
      (node (ref "C10") (pin "2") (pinfunction "2_2") (pintype "passive"))
      (node (ref "C11") (pin "2") (pinfunction "2_2") (pintype "passive"))
      (node (ref "C12") (pin "2") (pinfunction "2_2") (pintype "passive"))
      (node (ref "C13") (pin "2") (pinfunction "2_2") (pintype "passive"))
      (node (ref "C14") (pin "2") (pinfunction "2_2") (pintype "passive"))
      (node (ref "C15") (pin "2") (pinfunction "2_2") (pintype "passive"))
      (node (ref "C16") (pin "2") (pinfunction "2_2") (pintype "passive"))
      (node (ref "C17") (pin "2") (pinfunction "2_2") (pintype "passive"))
      (node (ref "C18") (pin "2") (pinfunction "2_2") (pintype "passive"))
      (node (ref "C19") (pin "2") (pinfunction "2_2") (pintype "passive"))
      (node (ref "C2") (pin "-") (pinfunction "-_-") (pintype "passive"))
      (node (ref "C20") (pin "2") (pinfunction "2_2") (pintype "passive"))
      (node (ref "C21") (pin "2") (pinfunction "2_2") (pintype "passive"))
      (node (ref "C22") (pin "2") (pinfunction "2_2") (pintype "passive"))
      (node (ref "C23") (pin "2") (pinfunction "2_2") (pintype "passive"))
      (node (ref "C24") (pin "2") (pinfunction "2_2") (pintype "passive"))
      (node (ref "C25") (pin "2") (pinfunction "2_2") (pintype "passive"))
      (node (ref "C26") (pin "2") (pinfunction "2_2") (pintype "passive"))
      (node (ref "C27") (pin "2") (pinfunction "2_2") (pintype "passive"))
      (node (ref "C28") (pin "1") (pinfunction "1_1") (pintype "passive"))
      (node (ref "C29") (pin "1") (pinfunction "1_1") (pintype "passive"))
      (node (ref "C30") (pin "1") (pinfunction "1_1") (pintype "passive"))
      (node (ref "C31") (pin "1") (pinfunction "1_1") (pintype "passive"))
      (node (ref "C32") (pin "C") (pinfunction "-_C") (pintype "passive"))
      (node (ref "C33") (pin "2") (pinfunction "2_2") (pintype "passive"))
      (node (ref "C34") (pin "2") (pinfunction "2_2") (pintype "passive"))
      (node (ref "C35") (pin "C") (pinfunction "-_C") (pintype "passive"))
      (node (ref "C36") (pin "1") (pinfunction "1_1") (pintype "passive"))
      (node (ref "C37") (pin "C") (pinfunction "-_C") (pintype "passive"))
      (node (ref "C38") (pin "C") (pinfunction "-_C") (pintype "passive"))
      (node (ref "C39") (pin "C") (pinfunction "-_C") (pintype "passive"))
      (node (ref "C40") (pin "-") (pinfunction "-_-") (pintype "passive"))
      (node (ref "C41") (pin "-") (pinfunction "-_-") (pintype "passive"))
      (node (ref "C42") (pin "-") (pinfunction "-_-") (pintype "passive"))
      (node (ref "C43") (pin "2") (pinfunction "2_2") (pintype "passive"))
      (node (ref "C44") (pin "C") (pinfunction "-_C") (pintype "passive"))
      (node (ref "C45") (pin "2") (pinfunction "2_2") (pintype "passive"))
      (node (ref "C47") (pin "C") (pinfunction "-_C") (pintype "passive"))
      (node (ref "C48") (pin "C") (pinfunction "-_C") (pintype "passive"))
      (node (ref "C49") (pin "2") (pinfunction "2_2") (pintype "passive"))
      (node (ref "C5") (pin "2") (pinfunction "2_2") (pintype "passive"))
      (node (ref "C50") (pin "2") (pinfunction "2_2") (pintype "passive"))
      (node (ref "C51") (pin "C") (pinfunction "-_C") (pintype "passive"))
      (node (ref "C52") (pin "C") (pinfunction "-_C") (pintype "passive"))
      (node (ref "C56") (pin "-") (pinfunction "-_-") (pintype "passive"))
      (node (ref "C6") (pin "2") (pinfunction "2_2") (pintype "passive"))
      (node (ref "C7") (pin "2") (pinfunction "2_2") (pintype "passive"))
      (node (ref "C8") (pin "2") (pinfunction "2_2") (pintype "passive"))
      (node (ref "C9") (pin "2") (pinfunction "2_2") (pintype "passive"))
      (node (ref "D14") (pin "A") (pinfunction "A_A") (pintype "passive"))
      (node (ref "D18") (pin "2") (pinfunction "A_2") (pintype "passive"))
      (node (ref "IC1") (pin "8") (pinfunction "VSS_8") (pintype "power_in"))
      (node (ref "IC2") (pin "1") (pinfunction "ADJ_1") (pintype "input"))
      (node (ref "IC3") (pin "11") (pinfunction "GND_11") (pintype "power_in"))
      (node (ref "IC3") (pin "32") (pinfunction "GND1_32") (pintype "power_in"))
      (node (ref "IC3") (pin "62") (pinfunction "GND2_62") (pintype "power_in"))
      (node (ref "IC3") (pin "81") (pinfunction "GND3_81") (pintype "power_in"))
      (node (ref "IC3") (pin "99") (pinfunction "AGND_99") (pintype "power_in"))
      (node (ref "IC5") (pin "2") (pinfunction "-IN_2") (pintype "input"))
      (node (ref "IC5") (pin "3") (pinfunction "+IN_3") (pintype "input"))
      (node (ref "IC5") (pin "4") (pinfunction "V-_4") (pintype "power_in"))
      (node (ref "IC9") (pin "4") (pinfunction "EN_4") (pintype "bidirectional"))
      (node (ref "IC9") (pin "5") (pinfunction "GND1_5") (pintype "bidirectional"))
      (node (ref "IC9") (pin "6") (pinfunction "GND2_6") (pintype "bidirectional"))
      (node (ref "IC9") (pin "7") (pinfunction "GND3_7") (pintype "bidirectional"))
      (node (ref "IC9") (pin "8") (pinfunction "GND4_8") (pintype "bidirectional"))
      (node (ref "ICSP") (pin "6") (pinfunction "6_6") (pintype "passive"))
      (node (ref "J3") (pin "GND") (pinfunction "GND_GND") (pintype "bidirectional"))
      (node (ref "J3") (pin "GND2") (pinfunction "GND_GND2") (pintype "bidirectional"))
      (node (ref "J6") (pin "10") (pinfunction "10_10") (pintype "passive"))
      (node (ref "J7") (pin "10") (pinfunction "10_10") (pintype "passive"))
      (node (ref "J8") (pin "10") (pinfunction "10_10") (pintype "passive"))
      (node (ref "L") (pin "C") (pinfunction "C_C") (pintype "passive"))
      (node (ref "L3") (pin "2") (pinfunction "2_2") (pintype "passive"))
      (node (ref "MOS2") (pin "3") (pinfunction "S_3") (pintype "passive"))
      (node (ref "ON") (pin "C") (pinfunction "C_C") (pintype "passive"))
      (node (ref "PWRIN") (pin "1") (pinfunction "1_1") (pintype "passive"))
      (node (ref "Q1") (pin "3") (pinfunction "S_3") (pintype "passive"))
      (node (ref "Q2") (pin "3") (pinfunction "S_3") (pintype "passive"))
      (node (ref "Q22") (pin "3") (pinfunction "S_3") (pintype "passive"))
      (node (ref "R1") (pin "1") (pinfunction "1_1") (pintype "passive"))
      (node (ref "R17") (pin "1") (pinfunction "1_1") (pintype "passive"))
      (node (ref "R2") (pin "1") (pinfunction "1_1") (pintype "passive"))
      (node (ref "R25") (pin "1") (pinfunction "1_1") (pintype "passive"))
      (node (ref "R44") (pin "1") (pinfunction "1_1") (pintype "passive"))
      (node (ref "R5") (pin "1") (pinfunction "1_1") (pintype "passive"))
      (node (ref "R53") (pin "1") (pinfunction "1_1") (pintype "passive"))
      (node (ref "R63") (pin "1") (pinfunction "1_1") (pintype "passive"))
      (node (ref "R67") (pin "1") (pinfunction "1_1") (pintype "passive"))
      (node (ref "R7") (pin "1") (pinfunction "1_1") (pintype "passive"))
      (node (ref "R70") (pin "1") (pinfunction "1_1") (pintype "passive"))
      (node (ref "R71") (pin "1") (pinfunction "1_1") (pintype "passive"))
      (node (ref "RESET") (pin "1") (pinfunction "1_1") (pintype "passive"))
      (node (ref "RESET") (pin "2") (pinfunction "2_2") (pintype "passive"))
      (node (ref "SJ1") (pin "1") (pinfunction "1_1") (pintype "passive"))
      (node (ref "SJ2") (pin "1") (pinfunction "1_1") (pintype "passive"))
      (node (ref "SJ3") (pin "1") (pinfunction "1_1") (pintype "passive"))
      (node (ref "SJ4") (pin "1") (pinfunction "1_1") (pintype "passive"))
      (node (ref "SJ5") (pin "1") (pinfunction "1_1") (pintype "passive"))
      (node (ref "SJ6") (pin "1") (pinfunction "1_1") (pintype "passive"))
      (node (ref "SJ7") (pin "1") (pinfunction "1_1") (pintype "passive"))
      (node (ref "SJ8") (pin "1") (pinfunction "1_1") (pintype "passive"))
      (node (ref "U$1") (pin "GND") (pinfunction "GND1_GND") (pintype "bidirectional"))
      (node (ref "U$1") (pin "GND-PAD") (pinfunction "GNDPAD_GND-PAD") (pintype "bidirectional"))
      (node (ref "U$1") (pin "GND2") (pinfunction "GND2_GND2") (pintype "bidirectional"))
      (node (ref "U$1") (pin "GND3") (pinfunction "GND3_GND3") (pintype "bidirectional"))
      (node (ref "U$1") (pin "GND4") (pinfunction "GND4_GND4") (pintype "bidirectional"))
      (node (ref "U$1") (pin "GND5") (pinfunction "GND5_GND5") (pintype "bidirectional"))
      (node (ref "U$1") (pin "GND6") (pinfunction "GND6_GND6") (pintype "bidirectional"))
      (node (ref "U$17") (pin "GND") (pinfunction "GND1_GND") (pintype "bidirectional"))
      (node (ref "U$17") (pin "GND-PAD") (pinfunction "GNDPAD_GND-PAD") (pintype "bidirectional"))
      (node (ref "U$17") (pin "GND2") (pinfunction "GND2_GND2") (pintype "bidirectional"))
      (node (ref "U$17") (pin "GND3") (pinfunction "GND3_GND3") (pintype "bidirectional"))
      (node (ref "U$17") (pin "GND4") (pinfunction "GND4_GND4") (pintype "bidirectional"))
      (node (ref "U$17") (pin "GND5") (pinfunction "GND5_GND5") (pintype "bidirectional"))
      (node (ref "U$17") (pin "GND6") (pinfunction "GND6_GND6") (pintype "bidirectional"))
      (node (ref "U$2") (pin "GND") (pinfunction "GND1_GND") (pintype "bidirectional"))
      (node (ref "U$2") (pin "GND-PAD") (pinfunction "GNDPAD_GND-PAD") (pintype "bidirectional"))
      (node (ref "U$2") (pin "GND2") (pinfunction "GND2_GND2") (pintype "bidirectional"))
      (node (ref "U$2") (pin "GND3") (pinfunction "GND3_GND3") (pintype "bidirectional"))
      (node (ref "U$2") (pin "GND4") (pinfunction "GND4_GND4") (pintype "bidirectional"))
      (node (ref "U$2") (pin "GND5") (pinfunction "GND5_GND5") (pintype "bidirectional"))
      (node (ref "U$2") (pin "GND6") (pinfunction "GND6_GND6") (pintype "bidirectional"))
      (node (ref "U$7") (pin "GND") (pinfunction "GND1_GND") (pintype "bidirectional"))
      (node (ref "U$7") (pin "GND-PAD") (pinfunction "GNDPAD_GND-PAD") (pintype "bidirectional"))
      (node (ref "U$7") (pin "GND2") (pinfunction "GND2_GND2") (pintype "bidirectional"))
      (node (ref "U$7") (pin "GND3") (pinfunction "GND3_GND3") (pintype "bidirectional"))
      (node (ref "U$7") (pin "GND4") (pinfunction "GND4_GND4") (pintype "bidirectional"))
      (node (ref "U$7") (pin "GND5") (pinfunction "GND5_GND5") (pintype "bidirectional"))
      (node (ref "U$7") (pin "GND6") (pinfunction "GND6_GND6") (pintype "bidirectional"))
      (node (ref "U1") (pin "11") (pinfunction "11_11") (pintype "passive"))
      (node (ref "U1") (pin "13") (pinfunction "13_13") (pintype "passive"))
      (node (ref "U1") (pin "15") (pinfunction "15_15") (pintype "passive"))
      (node (ref "U1") (pin "9") (pinfunction "9_9") (pintype "passive"))
      (node (ref "U2") (pin "6") (pinfunction "GND_6") (pintype "bidirectional"))
      (node (ref "U2") (pin "GND1") (pinfunction "SHIELD_GND1") (pintype "bidirectional"))
      (node (ref "U2") (pin "GND2") (pinfunction "SHIELD_GND2") (pintype "bidirectional"))
      (node (ref "U6") (pin "18") (pinfunction "GND18_18") (pintype "power_in"))
      (node (ref "U6") (pin "21") (pinfunction "GND21_21") (pintype "power_in"))
      (node (ref "U6") (pin "25") (pinfunction "AGND_25") (pintype "power_in"))
      (node (ref "U6") (pin "26") (pinfunction "TEST_26") (pintype "input"))
      (node (ref "U6") (pin "7") (pinfunction "GND7_7") (pintype "power_in"))
      (node (ref "Z-CONN1") (pin "10") (pinfunction "10_10") (pintype "passive"))
    )
    (net (code "96") (name "HOTEND-NEG1") (class "Default")
      (node (ref "D3") (pin "A") (pinfunction "A_A") (pintype "passive"))
      (node (ref "J1") (pin "1") (pinfunction "1_1") (pintype "passive"))
      (node (ref "J1") (pin "2") (pinfunction "2_2") (pintype "passive"))
      (node (ref "J1") (pin "3") (pinfunction "3_3") (pintype "passive"))
      (node (ref "J1") (pin "4") (pinfunction "4_4") (pintype "passive"))
      (node (ref "Q2") (pin "4") (pinfunction "D_4") (pintype "passive"))
      (node (ref "X-END1") (pin "1") (pinfunction "1_1") (pintype "passive"))
    )
    (net (code "97") (name "M8RXD") (class "Default")
      (node (ref "R68") (pin "1") (pinfunction "1_1") (pintype "passive"))
      (node (ref "U6") (pin "1") (pinfunction "TXD_1") (pintype "output"))
    )
    (net (code "98") (name "M8TXD") (class "Default")
      (node (ref "R69") (pin "1") (pinfunction "1_1") (pintype "passive"))
      (node (ref "U6") (pin "5") (pinfunction "RXD_5") (pintype "input"))
    )
    (net (code "99") (name "Net-(C11-Pad1)") (class "Default")
      (node (ref "C11") (pin "1") (pinfunction "1_1") (pintype "passive"))
      (node (ref "R3") (pin "S") (pinfunction "S_S") (pintype "passive"))
      (node (ref "U$17") (pin "VREFA") (pinfunction "VREFA_VREFA") (pintype "bidirectional"))
      (node (ref "U$17") (pin "VREFB") (pinfunction "VREFB_VREFB") (pintype "bidirectional"))
    )
    (net (code "100") (name "Net-(C12-Pad1)") (class "Default")
      (node (ref "C12") (pin "1") (pinfunction "1_1") (pintype "passive"))
      (node (ref "R12") (pin "1") (pinfunction "1_1") (pintype "passive"))
      (node (ref "U$17") (pin "OSCM") (pinfunction "OSCM_OSCM") (pintype "bidirectional"))
    )
    (net (code "101") (name "Net-(C17-Pad1)") (class "Default")
      (node (ref "C17") (pin "1") (pinfunction "1_1") (pintype "passive"))
      (node (ref "R4") (pin "S") (pinfunction "S_S") (pintype "passive"))
      (node (ref "U$1") (pin "VREFA") (pinfunction "VREFA_VREFA") (pintype "bidirectional"))
      (node (ref "U$1") (pin "VREFB") (pinfunction "VREFB_VREFB") (pintype "bidirectional"))
    )
    (net (code "102") (name "Net-(C18-Pad1)") (class "Default")
      (node (ref "C18") (pin "1") (pinfunction "1_1") (pintype "passive"))
      (node (ref "R32") (pin "1") (pinfunction "1_1") (pintype "passive"))
      (node (ref "U$1") (pin "OSCM") (pinfunction "OSCM_OSCM") (pintype "bidirectional"))
    )
    (net (code "103") (name "Net-(C22-Pad1)") (class "Default")
      (node (ref "C22") (pin "1") (pinfunction "1_1") (pintype "passive"))
      (node (ref "R20") (pin "S") (pinfunction "S_S") (pintype "passive"))
      (node (ref "U$2") (pin "VREFA") (pinfunction "VREFA_VREFA") (pintype "bidirectional"))
      (node (ref "U$2") (pin "VREFB") (pinfunction "VREFB_VREFB") (pintype "bidirectional"))
    )
    (net (code "104") (name "Net-(C23-Pad1)") (class "Default")
      (node (ref "C23") (pin "1") (pinfunction "1_1") (pintype "passive"))
      (node (ref "R41") (pin "1") (pinfunction "1_1") (pintype "passive"))
      (node (ref "U$2") (pin "OSCM") (pinfunction "OSCM_OSCM") (pintype "bidirectional"))
    )
    (net (code "105") (name "Net-(C27-Pad1)") (class "Default")
      (node (ref "C27") (pin "1") (pinfunction "1_1") (pintype "passive"))
      (node (ref "R21") (pin "S") (pinfunction "S_S") (pintype "passive"))
      (node (ref "U$7") (pin "VREFA") (pinfunction "VREFA_VREFA") (pintype "bidirectional"))
      (node (ref "U$7") (pin "VREFB") (pinfunction "VREFB_VREFB") (pintype "bidirectional"))
    )
    (net (code "106") (name "Net-(C33-Pad1)") (class "Default")
      (node (ref "C33") (pin "1") (pinfunction "1_1") (pintype "passive"))
      (node (ref "R50") (pin "1") (pinfunction "1_1") (pintype "passive"))
      (node (ref "U$7") (pin "OSCM") (pinfunction "OSCM_OSCM") (pintype "bidirectional"))
    )
    (net (code "107") (name "Net-(D11-C)") (class "Default")
      (node (ref "D11") (pin "1") (pinfunction "C_1") (pintype "passive"))
      (node (ref "IC9") (pin "1") (pinfunction "IN_1") (pintype "bidirectional"))
    )
    (net (code "108") (name "Net-(D15-C)") (class "Default")
      (node (ref "D15") (pin "1") (pinfunction "C_1") (pintype "passive"))
      (node (ref "T2") (pin "1") (pinfunction "D_1") (pintype "passive"))
    )
    (net (code "109") (name "Net-(D16-PadA)") (class "Default")
      (node (ref "D16") (pin "A") (pinfunction "A_A") (pintype "passive"))
      (node (ref "U1") (pin "2") (pinfunction "2_2") (pintype "passive"))
    )
    (net (code "110") (name "Net-(D17-PadA)") (class "Default")
      (node (ref "D17") (pin "A") (pinfunction "A_A") (pintype "passive"))
      (node (ref "U1") (pin "4") (pinfunction "4_4") (pintype "passive"))
    )
    (net (code "111") (name "Net-(D18-C)") (class "Default")
      (node (ref "D18") (pin "1") (pinfunction "C_1") (pintype "passive"))
      (node (ref "IC9") (pin "2") (pinfunction "OUT_2") (pintype "bidirectional"))
      (node (ref "L2") (pin "2") (pinfunction "2_2") (pintype "passive"))
    )
    (net (code "112") (name "Net-(D19-PadA)") (class "Default")
      (node (ref "D19") (pin "A") (pinfunction "A_A") (pintype "passive"))
      (node (ref "U1") (pin "6") (pinfunction "6_6") (pintype "passive"))
    )
    (net (code "113") (name "Net-(D20-PadA)") (class "Default")
      (node (ref "D20") (pin "A") (pinfunction "A_A") (pintype "passive"))
      (node (ref "U1") (pin "8") (pinfunction "8_8") (pintype "passive"))
    )
    (net (code "114") (name "Net-(D21-C1)") (class "Default")
      (node (ref "D21") (pin "3") (pinfunction "C1_3") (pintype "bidirectional"))
      (node (ref "R73") (pin "2") (pinfunction "2_2") (pintype "passive"))
    )
    (net (code "115") (name "Net-(D21-C2)") (class "Default")
      (node (ref "D21") (pin "4") (pinfunction "C2_4") (pintype "bidirectional"))
      (node (ref "R72") (pin "2") (pinfunction "2_2") (pintype "passive"))
    )
    (net (code "116") (name "Net-(J3-CC1)") (class "Default")
      (node (ref "J3") (pin "A5") (pinfunction "CC1_A5") (pintype "bidirectional"))
      (node (ref "R71") (pin "2") (pinfunction "2_2") (pintype "passive"))
    )
    (net (code "117") (name "Net-(J3-CC2)") (class "Default")
      (node (ref "J3") (pin "B5") (pinfunction "CC2_B5") (pintype "bidirectional"))
      (node (ref "R70") (pin "2") (pinfunction "2_2") (pintype "passive"))
    )
    (net (code "118") (name "Net-(L-PadA)") (class "Default")
      (node (ref "L") (pin "A") (pinfunction "A_A") (pintype "passive"))
      (node (ref "R55") (pin "2") (pinfunction "2_2") (pintype "passive"))
    )
    (net (code "119") (name "Net-(LED6-C)") (class "Default")
      (node (ref "LED6") (pin "K") (pinfunction "C_K") (pintype "passive"))
      (node (ref "R2") (pin "2") (pinfunction "2_2") (pintype "passive"))
    )
    (net (code "120") (name "Net-(MOS2-G)") (class "Default")
      (node (ref "MOS2") (pin "1") (pinfunction "G_1") (pintype "passive"))
      (node (ref "R24") (pin "2") (pinfunction "2_2") (pintype "passive"))
      (node (ref "R25") (pin "2") (pinfunction "2_2") (pintype "passive"))
    )
    (net (code "121") (name "Net-(ON-PadA)") (class "Default")
      (node (ref "ON") (pin "A") (pinfunction "A_A") (pintype "passive"))
      (node (ref "R60") (pin "2") (pinfunction "2_2") (pintype "passive"))
    )
    (net (code "122") (name "Net-(Q1-G)") (class "Default")
      (node (ref "Q1") (pin "1") (pinfunction "G_1") (pintype "passive"))
      (node (ref "R35") (pin "1") (pinfunction "1_1") (pintype "passive"))
      (node (ref "R53") (pin "2") (pinfunction "2_2") (pintype "passive"))
    )
    (net (code "123") (name "Net-(Q2-G)") (class "Default")
      (node (ref "Q2") (pin "1") (pinfunction "G_1") (pintype "passive"))
      (node (ref "R62") (pin "2") (pinfunction "2_2") (pintype "passive"))
      (node (ref "R63") (pin "2") (pinfunction "2_2") (pintype "passive"))
    )
    (net (code "124") (name "Net-(Q22-G)") (class "Default")
      (node (ref "Q22") (pin "1") (pinfunction "G_1") (pintype "passive"))
      (node (ref "R28") (pin "1") (pinfunction "1_1") (pintype "passive"))
      (node (ref "R44") (pin "2") (pinfunction "2_2") (pintype "passive"))
    )
    (net (code "125") (name "Net-(R1-Pad2)") (class "Default")
      (node (ref "R1") (pin "2") (pinfunction "2_2") (pintype "passive"))
      (node (ref "R4") (pin "A") (pinfunction "A_A") (pintype "passive"))
    )
    (net (code "126") (name "Net-(R10-Pad1)") (class "Default")
      (node (ref "R10") (pin "1") (pinfunction "1_1") (pintype "passive"))
      (node (ref "U$17") (pin "RSB1") (pinfunction "RSB1_RSB1") (pintype "bidirectional"))
      (node (ref "U$17") (pin "RSB2") (pinfunction "RSB2_RSB2") (pintype "bidirectional"))
    )
    (net (code "127") (name "Net-(R14-Pad1)") (class "Default")
      (node (ref "R14") (pin "1") (pinfunction "1_1") (pintype "passive"))
      (node (ref "U$17") (pin "MO") (pinfunction "MO_MO") (pintype "bidirectional"))
    )
    (net (code "128") (name "Net-(R17-Pad2)") (class "Default")
      (node (ref "R17") (pin "2") (pinfunction "2_2") (pintype "passive"))
      (node (ref "R3") (pin "A") (pinfunction "A_A") (pintype "passive"))
    )
    (net (code "129") (name "Net-(R18-Pad1)") (class "Default")
      (node (ref "R18") (pin "1") (pinfunction "1_1") (pintype "passive"))
      (node (ref "R3") (pin "E") (pinfunction "E_E") (pintype "passive"))
    )
    (net (code "130") (name "Net-(R19-Pad1)") (class "Default")
      (node (ref "R19") (pin "1") (pinfunction "1_1") (pintype "passive"))
      (node (ref "R4") (pin "E") (pinfunction "E_E") (pintype "passive"))
    )
    (net (code "131") (name "Net-(R20-PadA)") (class "Default")
      (node (ref "R20") (pin "A") (pinfunction "A_A") (pintype "passive"))
      (node (ref "R5") (pin "2") (pinfunction "2_2") (pintype "passive"))
    )
    (net (code "132") (name "Net-(R20-PadE)") (class "Default")
      (node (ref "R20") (pin "E") (pinfunction "E_E") (pintype "passive"))
      (node (ref "R22") (pin "1") (pinfunction "1_1") (pintype "passive"))
    )
    (net (code "133") (name "Net-(R21-PadA)") (class "Default")
      (node (ref "R21") (pin "A") (pinfunction "A_A") (pintype "passive"))
      (node (ref "R7") (pin "2") (pinfunction "2_2") (pintype "passive"))
    )
    (net (code "134") (name "Net-(R21-PadE)") (class "Default")
      (node (ref "R21") (pin "E") (pinfunction "E_E") (pintype "passive"))
      (node (ref "R23") (pin "1") (pinfunction "1_1") (pintype "passive"))
    )
    (net (code "135") (name "Net-(R30-Pad1)") (class "Default")
      (node (ref "R30") (pin "1") (pinfunction "1_1") (pintype "passive"))
      (node (ref "U$1") (pin "RSB1") (pinfunction "RSB1_RSB1") (pintype "bidirectional"))
      (node (ref "U$1") (pin "RSB2") (pinfunction "RSB2_RSB2") (pintype "bidirectional"))
    )
    (net (code "136") (name "Net-(R34-Pad1)") (class "Default")
      (node (ref "R34") (pin "1") (pinfunction "1_1") (pintype "passive"))
      (node (ref "U$1") (pin "MO") (pinfunction "MO_MO") (pintype "bidirectional"))
    )
    (net (code "137") (name "Net-(R43-Pad1)") (class "Default")
      (node (ref "R43") (pin "1") (pinfunction "1_1") (pintype "passive"))
      (node (ref "U$2") (pin "MO") (pinfunction "MO_MO") (pintype "bidirectional"))
    )
    (net (code "138") (name "Net-(R52-Pad1)") (class "Default")
      (node (ref "R52") (pin "1") (pinfunction "1_1") (pintype "passive"))
      (node (ref "U$7") (pin "MO") (pinfunction "MO_MO") (pintype "bidirectional"))
    )
    (net (code "139") (name "Net-(R74-Pad2)") (class "Default")
      (node (ref "R74") (pin "2") (pinfunction "2_2") (pintype "passive"))
      (node (ref "U1") (pin "1") (pinfunction "1_1") (pintype "passive"))
    )
    (net (code "140") (name "Net-(R75-Pad2)") (class "Default")
      (node (ref "R75") (pin "2") (pinfunction "2_2") (pintype "passive"))
      (node (ref "U1") (pin "3") (pinfunction "3_3") (pintype "passive"))
    )
    (net (code "141") (name "Net-(R76-Pad2)") (class "Default")
      (node (ref "R76") (pin "2") (pinfunction "2_2") (pintype "passive"))
      (node (ref "U1") (pin "5") (pinfunction "5_5") (pintype "passive"))
    )
    (net (code "142") (name "Net-(R77-Pad2)") (class "Default")
      (node (ref "R77") (pin "2") (pinfunction "2_2") (pintype "passive"))
      (node (ref "U1") (pin "7") (pinfunction "7_7") (pintype "passive"))
    )
    (net (code "143") (name "Net-(U$1-RSA1)") (class "Default")
      (node (ref "R31") (pin "1") (pinfunction "1_1") (pintype "passive"))
      (node (ref "U$1") (pin "RSA") (pinfunction "RSA1_RSA") (pintype "bidirectional"))
      (node (ref "U$1") (pin "RSA2") (pinfunction "RSA2_RSA2") (pintype "bidirectional"))
    )
    (net (code "144") (name "Net-(U$17-RSA1)") (class "Default")
      (node (ref "R11") (pin "1") (pinfunction "1_1") (pintype "passive"))
      (node (ref "U$17") (pin "RSA") (pinfunction "RSA1_RSA") (pintype "bidirectional"))
      (node (ref "U$17") (pin "RSA2") (pinfunction "RSA2_RSA2") (pintype "bidirectional"))
    )
    (net (code "145") (name "PART-FAN-NEG") (class "Default")
      (node (ref "D12") (pin "A") (pinfunction "A_A") (pintype "passive"))
      (node (ref "J2") (pin "5") (pinfunction "5_5") (pintype "passive"))
      (node (ref "J2") (pin "6") (pinfunction "6_6") (pintype "passive"))
      (node (ref "Q22") (pin "4") (pinfunction "D_4") (pintype "passive"))
      (node (ref "X-END2") (pin "1") (pinfunction "1_1") (pintype "passive"))
    )
    (net (code "146") (name "PH3") (class "Default")
      (node (ref "IC3") (pin "15") (pinfunction "PH3(OC4A)_15") (pintype "bidirectional"))
    )
    (net (code "147") (name "PH4") (class "Default")
      (node (ref "IC3") (pin "16") (pinfunction "PH4(OC4B)_16") (pintype "bidirectional"))
    )
    (net (code "148") (name "RESET") (class "Default")
      (node (ref "C14") (pin "1") (pinfunction "1_1") (pintype "passive"))
      (node (ref "C46") (pin "2") (pinfunction "2_2") (pintype "passive"))
      (node (ref "IC3") (pin "30") (pinfunction "RESET_30") (pintype "input"))
      (node (ref "ICSP") (pin "5") (pinfunction "5_5") (pintype "passive"))
      (node (ref "R61") (pin "1") (pinfunction "1_1") (pintype "passive"))
      (node (ref "RESET") (pin "3") (pinfunction "3_3") (pintype "passive"))
      (node (ref "RESET") (pin "4") (pinfunction "4_4") (pintype "passive"))
    )
    (net (code "149") (name "RTS") (class "Default")
      (node (ref "U6") (pin "3") (pinfunction "RTS_3") (pintype "output"))
    )
    (net (code "150") (name "RXLED") (class "Default")
      (node (ref "R72") (pin "1") (pinfunction "1_1") (pintype "passive"))
      (node (ref "U6") (pin "22") (pinfunction "RXLED_22") (pintype "input"))
    )
    (net (code "151") (name "SC") (class "Default")
      (node (ref "IC1") (pin "6") (pinfunction "O_6") (pintype "output"))
      (node (ref "U2") (pin "5") (pinfunction "SCK_5") (pintype "bidirectional"))
    )
    (net (code "152") (name "SHLD") (class "Default")
      (node (ref "J3") (pin "SHLD1") (pinfunction "SHLD_SHLD1") (pintype "bidirectional"))
      (node (ref "J3") (pin "SHLD2") (pinfunction "SHLD_SHLD2") (pintype "bidirectional"))
      (node (ref "J3") (pin "SHLD3") (pinfunction "SHLD_SHLD3") (pintype "bidirectional"))
      (node (ref "J3") (pin "SHLD4") (pinfunction "SHLD_SHLD4") (pintype "bidirectional"))
      (node (ref "J3") (pin "SHLD5") (pinfunction "SHLD_SHLD5") (pintype "bidirectional"))
      (node (ref "J3") (pin "SHLD6") (pinfunction "SHLD_SHLD6") (pintype "bidirectional"))
      (node (ref "J3") (pin "SHLD7") (pinfunction "SHLD_SHLD7") (pintype "bidirectional"))
      (node (ref "J3") (pin "SHLD8") (pinfunction "SHLD_SHLD8") (pintype "bidirectional"))
    )
    (net (code "153") (name "SPARE1") (class "Default")
      (node (ref "J2") (pin "10") (pinfunction "10_10") (pintype "passive"))
    )
    (net (code "154") (name "SPARE2") (class "Default")
      (node (ref "J2") (pin "9") (pinfunction "9_9") (pintype "passive"))
    )
    (net (code "155") (name "TXLED") (class "Default")
      (node (ref "R73") (pin "1") (pinfunction "1_1") (pintype "passive"))
      (node (ref "U6") (pin "23") (pinfunction "TXLED_23") (pintype "input"))
    )
    (net (code "156") (name "V+PSU") (class "Default")
      (node (ref "PWRIN") (pin "2") (pinfunction "1_2") (pintype "passive"))
      (node (ref "U$4") (pin "TERM1.1") (pinfunction "P$1_TERM1.1") (pintype "bidirectional"))
      (node (ref "U$4") (pin "TERM1.2") (pinfunction "P$1_TERM1.2") (pintype "bidirectional"))
    )
    (net (code "157") (name "VM") (class "Default")
      (node (ref "BED") (pin "2") (pinfunction "1_2") (pintype "passive"))
      (node (ref "C1") (pin "+") (pinfunction "+_+") (pintype "passive"))
      (node (ref "C10") (pin "1") (pinfunction "1_1") (pintype "passive"))
      (node (ref "C16") (pin "1") (pinfunction "1_1") (pintype "passive"))
      (node (ref "C2") (pin "+") (pinfunction "+_+") (pintype "passive"))
      (node (ref "C21") (pin "1") (pinfunction "1_1") (pintype "passive"))
      (node (ref "C26") (pin "1") (pinfunction "1_1") (pintype "passive"))
      (node (ref "C32") (pin "A") (pinfunction "+_A") (pintype "passive"))
      (node (ref "C35") (pin "A") (pinfunction "+_A") (pintype "passive"))
      (node (ref "C37") (pin "A") (pinfunction "+_A") (pintype "passive"))
      (node (ref "C38") (pin "A") (pinfunction "+_A") (pintype "passive"))
      (node (ref "C39") (pin "A") (pinfunction "+_A") (pintype "passive"))
      (node (ref "C40") (pin "+") (pinfunction "+_+") (pintype "passive"))
      (node (ref "C41") (pin "+") (pinfunction "+_+") (pintype "passive"))
      (node (ref "C42") (pin "+") (pinfunction "+_+") (pintype "passive"))
      (node (ref "C48") (pin "A") (pinfunction "+_A") (pintype "passive"))
      (node (ref "D11") (pin "2") (pinfunction "A_2") (pintype "passive"))
      (node (ref "D12") (pin "C") (pinfunction "C_C") (pintype "passive"))
      (node (ref "D13") (pin "C") (pinfunction "C_C") (pintype "passive"))
      (node (ref "D14") (pin "C") (pinfunction "C_C") (pintype "passive"))
      (node (ref "D2") (pin "C") (pinfunction "C_C") (pintype "passive"))
      (node (ref "D3") (pin "C") (pinfunction "C_C") (pintype "passive"))
      (node (ref "J1") (pin "5") (pinfunction "5_5") (pintype "passive"))
      (node (ref "J1") (pin "6") (pinfunction "6_6") (pintype "passive"))
      (node (ref "J1") (pin "7") (pinfunction "7_7") (pintype "passive"))
      (node (ref "J1") (pin "8") (pinfunction "8_8") (pintype "passive"))
      (node (ref "J2") (pin "3") (pinfunction "3_3") (pintype "passive"))
      (node (ref "J2") (pin "4") (pinfunction "4_4") (pintype "passive"))
      (node (ref "J2") (pin "7") (pinfunction "7_7") (pintype "passive"))
      (node (ref "J2") (pin "8") (pinfunction "8_8") (pintype "passive"))
      (node (ref "LED6") (pin "A") (pinfunction "A_A") (pintype "passive"))
      (node (ref "R10") (pin "2") (pinfunction "2_2") (pintype "passive"))
      (node (ref "R11") (pin "2") (pinfunction "2_2") (pintype "passive"))
      (node (ref "R30") (pin "2") (pinfunction "2_2") (pintype "passive"))
      (node (ref "R31") (pin "2") (pinfunction "2_2") (pintype "passive"))
      (node (ref "R39") (pin "2") (pinfunction "2_2") (pintype "passive"))
      (node (ref "R40") (pin "2") (pinfunction "2_2") (pintype "passive"))
      (node (ref "R48") (pin "2") (pinfunction "2_2") (pintype "passive"))
      (node (ref "R49") (pin "2") (pinfunction "2_2") (pintype "passive"))
      (node (ref "R66") (pin "2") (pinfunction "2_2") (pintype "passive"))
      (node (ref "U$1") (pin "VM") (pinfunction "VM_VM") (pintype "bidirectional"))
      (node (ref "U$17") (pin "VM") (pinfunction "VM_VM") (pintype "bidirectional"))
      (node (ref "U$2") (pin "VM") (pinfunction "VM_VM") (pintype "bidirectional"))
      (node (ref "U$4") (pin "TERM2.1") (pinfunction "P$2_TERM2.1") (pintype "bidirectional"))
      (node (ref "U$4") (pin "TERM2.2") (pinfunction "P$2_TERM2.2") (pintype "bidirectional"))
      (node (ref "U$7") (pin "VM") (pinfunction "VM_VM") (pintype "bidirectional"))
      (node (ref "X-END1") (pin "2") (pinfunction "1_2") (pintype "passive"))
      (node (ref "X-END2") (pin "2") (pinfunction "1_2") (pintype "passive"))
      (node (ref "X-END3") (pin "2") (pinfunction "1_2") (pintype "passive"))
    )
    (net (code "158") (name "V_USB") (class "Default")
      (node (ref "C43") (pin "1") (pinfunction "1_1") (pintype "passive"))
      (node (ref "C44") (pin "A") (pinfunction "+_A") (pintype "passive"))
      (node (ref "D15") (pin "2") (pinfunction "A_2") (pintype "passive"))
      (node (ref "D21") (pin "1") (pinfunction "A1_1") (pintype "bidirectional"))
      (node (ref "D21") (pin "2") (pinfunction "A2_2") (pintype "bidirectional"))
      (node (ref "J3") (pin "VBUS1") (pinfunction "VBUS_VBUS1") (pintype "bidirectional"))
      (node (ref "J3") (pin "VBUS2") (pinfunction "VBUS_VBUS2") (pintype "bidirectional"))
      (node (ref "U6") (pin "20") (pinfunction "VCC_20") (pintype "power_in"))
      (node (ref "U6") (pin "4") (pinfunction "VCCIO_4") (pintype "power_in"))
    )
    (net (code "159") (name "XFAULT") (class "Default")
      (node (ref "LED1") (pin "A") (pinfunction "A_A") (pintype "passive"))
      (node (ref "R56") (pin "1") (pinfunction "1_1") (pintype "passive"))
    )
    (net (code "160") (name "XLO") (class "Default")
      (node (ref "R13") (pin "1") (pinfunction "1_1") (pintype "passive"))
      (node (ref "R56") (pin "2") (pinfunction "2_2") (pintype "passive"))
      (node (ref "U$17") (pin "LO") (pinfunction "LO_LO") (pintype "bidirectional"))
    )
    (net (code "161") (name "XMODE0") (class "Default")
      (node (ref "R6") (pin "1") (pinfunction "1_1") (pintype "passive"))
      (node (ref "U$17") (pin "DMODE0") (pinfunction "DMODE0_DMODE0") (pintype "bidirectional"))
    )
    (net (code "162") (name "XMODE1") (class "Default")
      (node (ref "R8") (pin "1") (pinfunction "1_1") (pintype "passive"))
      (node (ref "SJ1") (pin "2") (pinfunction "2_2") (pintype "passive"))
      (node (ref "U$17") (pin "DMODE1") (pinfunction "DMODE1_DMODE1") (pintype "bidirectional"))
    )
    (net (code "163") (name "XMODE2") (class "Default")
      (node (ref "R9") (pin "1") (pinfunction "1_1") (pintype "passive"))
      (node (ref "SJ2") (pin "2") (pinfunction "2_2") (pintype "passive"))
      (node (ref "U$17") (pin "DMODE2") (pinfunction "DMODE2_DMODE2") (pintype "bidirectional"))
    )
    (net (code "164") (name "XOUT-A+") (class "Default")
      (node (ref "D1") (pin "C") (pinfunction "C_C") (pintype "passive"))
      (node (ref "U$17") (pin "OUTA+1") (pinfunction "OUTA+1_OUTA+1") (pintype "bidirectional"))
      (node (ref "U$17") (pin "OUTA+2") (pinfunction "OUTA+2_OUTA+2") (pintype "bidirectional"))
      (node (ref "Z-CONN1") (pin "1") (pinfunction "1_1") (pintype "passive"))
      (node (ref "Z-CONN1") (pin "2") (pinfunction "2_2") (pintype "passive"))
    )
    (net (code "165") (name "XOUT-A-") (class "Default")
      (node (ref "D1") (pin "A") (pinfunction "A_A") (pintype "passive"))
      (node (ref "U$17") (pin "OUTA-1") (pinfunction "OUTA-1_OUTA-1") (pintype "bidirectional"))
      (node (ref "U$17") (pin "OUTA-2") (pinfunction "OUTA-2_OUTA-2") (pintype "bidirectional"))
      (node (ref "Z-CONN1") (pin "3") (pinfunction "3_3") (pintype "passive"))
      (node (ref "Z-CONN1") (pin "4") (pinfunction "4_4") (pintype "passive"))
    )
    (net (code "166") (name "XOUT-B+") (class "Default")
      (node (ref "D4") (pin "A") (pinfunction "A_A") (pintype "passive"))
      (node (ref "U$17") (pin "OUTB+1") (pinfunction "OUTB+1_OUTB+1") (pintype "bidirectional"))
      (node (ref "U$17") (pin "OUTB+2") (pinfunction "OUTB+2_OUTB+2") (pintype "bidirectional"))
      (node (ref "Z-CONN1") (pin "7") (pinfunction "7_7") (pintype "passive"))
      (node (ref "Z-CONN1") (pin "8") (pinfunction "8_8") (pintype "passive"))
    )
    (net (code "167") (name "XOUT-B-") (class "Default")
      (node (ref "D4") (pin "C") (pinfunction "C_C") (pintype "passive"))
      (node (ref "U$17") (pin "OUTB-1") (pinfunction "OUTB-1_OUTB-1") (pintype "bidirectional"))
      (node (ref "U$17") (pin "OUTB-2") (pinfunction "OUTB-2_OUTB-2") (pintype "bidirectional"))
      (node (ref "Z-CONN1") (pin "5") (pinfunction "5_5") (pintype "passive"))
      (node (ref "Z-CONN1") (pin "6") (pinfunction "6_6") (pintype "passive"))
    )
    (net (code "168") (name "XTAL1") (class "Default")
      (node (ref "C31") (pin "2") (pinfunction "2_2") (pintype "passive"))
      (node (ref "Q3") (pin "2") (pinfunction "2_2") (pintype "passive"))
      (node (ref "R54") (pin "2") (pinfunction "2_2") (pintype "passive"))
    )
    (net (code "169") (name "XTAL1R") (class "Default")
      (node (ref "IC3") (pin "34") (pinfunction "XTAL1_34") (pintype "input"))
      (node (ref "R54") (pin "1") (pinfunction "1_1") (pintype "passive"))
    )
    (net (code "170") (name "XTAL2") (class "Default")
      (node (ref "C36") (pin "2") (pinfunction "2_2") (pintype "passive"))
      (node (ref "IC3") (pin "33") (pinfunction "XTAL2_33") (pintype "output"))
      (node (ref "Q3") (pin "1") (pinfunction "1_1") (pintype "passive"))
    )
    (net (code "171") (name "XVCCINT") (class "Default")
      (node (ref "C13") (pin "1") (pinfunction "1_1") (pintype "passive"))
      (node (ref "U$17") (pin "VCC") (pinfunction "VCC_VCC") (pintype "bidirectional"))
    )
    (net (code "172") (name "Y2FAULT") (class "Default")
      (node (ref "LED3") (pin "A") (pinfunction "A_A") (pintype "passive"))
      (node (ref "R58") (pin "1") (pinfunction "1_1") (pintype "passive"))
    )
    (net (code "173") (name "Y2LO") (class "Default")
      (node (ref "R42") (pin "1") (pinfunction "1_1") (pintype "passive"))
      (node (ref "R58") (pin "2") (pinfunction "2_2") (pintype "passive"))
      (node (ref "U$2") (pin "LO") (pinfunction "LO_LO") (pintype "bidirectional"))
    )
    (net (code "174") (name "Y2RSA2") (class "Default")
      (node (ref "R40") (pin "1") (pinfunction "1_1") (pintype "passive"))
      (node (ref "U$2") (pin "RSA") (pinfunction "RSA1_RSA") (pintype "bidirectional"))
      (node (ref "U$2") (pin "RSA2") (pinfunction "RSA2_RSA2") (pintype "bidirectional"))
    )
    (net (code "175") (name "Y2RSB2") (class "Default")
      (node (ref "R39") (pin "1") (pinfunction "1_1") (pintype "passive"))
      (node (ref "U$2") (pin "RSB1") (pinfunction "RSB1_RSB1") (pintype "bidirectional"))
      (node (ref "U$2") (pin "RSB2") (pinfunction "RSB2_RSB2") (pintype "bidirectional"))
    )
    (net (code "176") (name "Y2VCCINT") (class "Default")
      (node (ref "C24") (pin "1") (pinfunction "1_1") (pintype "passive"))
      (node (ref "U$2") (pin "VCC") (pinfunction "VCC_VCC") (pintype "bidirectional"))
    )
    (net (code "177") (name "YFAULT") (class "Default")
      (node (ref "LED2") (pin "A") (pinfunction "A_A") (pintype "passive"))
      (node (ref "R57") (pin "1") (pinfunction "1_1") (pintype "passive"))
    )
    (net (code "178") (name "YLO") (class "Default")
      (node (ref "R33") (pin "1") (pinfunction "1_1") (pintype "passive"))
      (node (ref "R57") (pin "2") (pinfunction "2_2") (pintype "passive"))
      (node (ref "U$1") (pin "LO") (pinfunction "LO_LO") (pintype "bidirectional"))
    )
    (net (code "179") (name "YMODE0") (class "Default")
      (node (ref "R15") (pin "1") (pinfunction "1_1") (pintype "passive"))
      (node (ref "U$1") (pin "DMODE0") (pinfunction "DMODE0_DMODE0") (pintype "bidirectional"))
    )
    (net (code "180") (name "YMODE1") (class "Default")
      (node (ref "R16") (pin "1") (pinfunction "1_1") (pintype "passive"))
      (node (ref "SJ3") (pin "2") (pinfunction "2_2") (pintype "passive"))
      (node (ref "U$1") (pin "DMODE1") (pinfunction "DMODE1_DMODE1") (pintype "bidirectional"))
    )
    (net (code "181") (name "YMODE2") (class "Default")
      (node (ref "R29") (pin "1") (pinfunction "1_1") (pintype "passive"))
      (node (ref "SJ4") (pin "2") (pinfunction "2_2") (pintype "passive"))
      (node (ref "U$1") (pin "DMODE2") (pinfunction "DMODE2_DMODE2") (pintype "bidirectional"))
    )
    (net (code "182") (name "YOUT-A+") (class "Default")
      (node (ref "D5") (pin "C") (pinfunction "C_C") (pintype "passive"))
      (node (ref "J6") (pin "1") (pinfunction "1_1") (pintype "passive"))
      (node (ref "J6") (pin "2") (pinfunction "2_2") (pintype "passive"))
      (node (ref "U$1") (pin "OUTA+1") (pinfunction "OUTA+1_OUTA+1") (pintype "bidirectional"))
      (node (ref "U$1") (pin "OUTA+2") (pinfunction "OUTA+2_OUTA+2") (pintype "bidirectional"))
    )
    (net (code "183") (name "YOUT-A-") (class "Default")
      (node (ref "D5") (pin "A") (pinfunction "A_A") (pintype "passive"))
      (node (ref "J6") (pin "3") (pinfunction "3_3") (pintype "passive"))
      (node (ref "J6") (pin "4") (pinfunction "4_4") (pintype "passive"))
      (node (ref "U$1") (pin "OUTA-1") (pinfunction "OUTA-1_OUTA-1") (pintype "bidirectional"))
      (node (ref "U$1") (pin "OUTA-2") (pinfunction "OUTA-2_OUTA-2") (pintype "bidirectional"))
    )
    (net (code "184") (name "YOUT-B+") (class "Default")
      (node (ref "D6") (pin "A") (pinfunction "A_A") (pintype "passive"))
      (node (ref "J6") (pin "7") (pinfunction "7_7") (pintype "passive"))
      (node (ref "J6") (pin "8") (pinfunction "8_8") (pintype "passive"))
      (node (ref "U$1") (pin "OUTB+1") (pinfunction "OUTB+1_OUTB+1") (pintype "bidirectional"))
      (node (ref "U$1") (pin "OUTB+2") (pinfunction "OUTB+2_OUTB+2") (pintype "bidirectional"))
    )
    (net (code "185") (name "YOUT-B-") (class "Default")
      (node (ref "D6") (pin "C") (pinfunction "C_C") (pintype "passive"))
      (node (ref "J6") (pin "5") (pinfunction "5_5") (pintype "passive"))
      (node (ref "J6") (pin "6") (pinfunction "6_6") (pintype "passive"))
      (node (ref "U$1") (pin "OUTB-1") (pinfunction "OUTB-1_OUTB-1") (pintype "bidirectional"))
      (node (ref "U$1") (pin "OUTB-2") (pinfunction "OUTB-2_OUTB-2") (pintype "bidirectional"))
    )
    (net (code "186") (name "YVCCINT") (class "Default")
      (node (ref "C19") (pin "1") (pinfunction "1_1") (pintype "passive"))
      (node (ref "U$1") (pin "VCC") (pinfunction "VCC_VCC") (pintype "bidirectional"))
    )
    (net (code "187") (name "ZFAULT") (class "Default")
      (node (ref "LED4") (pin "A") (pinfunction "A_A") (pintype "passive"))
      (node (ref "R59") (pin "1") (pinfunction "1_1") (pintype "passive"))
    )
    (net (code "188") (name "ZLO") (class "Default")
      (node (ref "R51") (pin "1") (pinfunction "1_1") (pintype "passive"))
      (node (ref "R59") (pin "2") (pinfunction "2_2") (pintype "passive"))
      (node (ref "U$7") (pin "LO") (pinfunction "LO_LO") (pintype "bidirectional"))
    )
    (net (code "189") (name "ZMODE0") (class "Default")
      (node (ref "R36") (pin "1") (pinfunction "1_1") (pintype "passive"))
      (node (ref "U$2") (pin "DMODE0") (pinfunction "DMODE0_DMODE0") (pintype "bidirectional"))
    )
    (net (code "190") (name "ZMODE1") (class "Default")
      (node (ref "R37") (pin "1") (pinfunction "1_1") (pintype "passive"))
      (node (ref "SJ7") (pin "2") (pinfunction "2_2") (pintype "passive"))
      (node (ref "U$2") (pin "DMODE1") (pinfunction "DMODE1_DMODE1") (pintype "bidirectional"))
    )
    (net (code "191") (name "ZMODE2") (class "Default")
      (node (ref "R38") (pin "1") (pinfunction "1_1") (pintype "passive"))
      (node (ref "SJ8") (pin "2") (pinfunction "2_2") (pintype "passive"))
      (node (ref "U$2") (pin "DMODE2") (pinfunction "DMODE2_DMODE2") (pintype "bidirectional"))
    )
    (net (code "192") (name "ZOUT-A+") (class "Default")
      (node (ref "D7") (pin "C") (pinfunction "C_C") (pintype "passive"))
      (node (ref "J8") (pin "1") (pinfunction "1_1") (pintype "passive"))
      (node (ref "J8") (pin "2") (pinfunction "2_2") (pintype "passive"))
      (node (ref "U$2") (pin "OUTA+1") (pinfunction "OUTA+1_OUTA+1") (pintype "bidirectional"))
      (node (ref "U$2") (pin "OUTA+2") (pinfunction "OUTA+2_OUTA+2") (pintype "bidirectional"))
    )
    (net (code "193") (name "ZOUT-A-") (class "Default")
      (node (ref "D7") (pin "A") (pinfunction "A_A") (pintype "passive"))
      (node (ref "J8") (pin "3") (pinfunction "3_3") (pintype "passive"))
      (node (ref "J8") (pin "4") (pinfunction "4_4") (pintype "passive"))
      (node (ref "U$2") (pin "OUTA-1") (pinfunction "OUTA-1_OUTA-1") (pintype "bidirectional"))
      (node (ref "U$2") (pin "OUTA-2") (pinfunction "OUTA-2_OUTA-2") (pintype "bidirectional"))
    )
    (net (code "194") (name "ZOUT-B+") (class "Default")
      (node (ref "D8") (pin "A") (pinfunction "A_A") (pintype "passive"))
      (node (ref "J8") (pin "7") (pinfunction "7_7") (pintype "passive"))
      (node (ref "J8") (pin "8") (pinfunction "8_8") (pintype "passive"))
      (node (ref "U$2") (pin "OUTB+1") (pinfunction "OUTB+1_OUTB+1") (pintype "bidirectional"))
      (node (ref "U$2") (pin "OUTB+2") (pinfunction "OUTB+2_OUTB+2") (pintype "bidirectional"))
    )
    (net (code "195") (name "ZOUT-B-") (class "Default")
      (node (ref "D8") (pin "C") (pinfunction "C_C") (pintype "passive"))
      (node (ref "J8") (pin "5") (pinfunction "5_5") (pintype "passive"))
      (node (ref "J8") (pin "6") (pinfunction "6_6") (pintype "passive"))
      (node (ref "U$2") (pin "OUTB-1") (pinfunction "OUTB-1_OUTB-1") (pintype "bidirectional"))
      (node (ref "U$2") (pin "OUTB-2") (pinfunction "OUTB-2_OUTB-2") (pintype "bidirectional"))
    )
    (net (code "196") (name "ZRSA3") (class "Default")
      (node (ref "R49") (pin "1") (pinfunction "1_1") (pintype "passive"))
      (node (ref "U$7") (pin "RSA") (pinfunction "RSA1_RSA") (pintype "bidirectional"))
      (node (ref "U$7") (pin "RSA2") (pinfunction "RSA2_RSA2") (pintype "bidirectional"))
    )
    (net (code "197") (name "ZRSB3") (class "Default")
      (node (ref "R48") (pin "1") (pinfunction "1_1") (pintype "passive"))
      (node (ref "U$7") (pin "RSB1") (pinfunction "RSB1_RSB1") (pintype "bidirectional"))
      (node (ref "U$7") (pin "RSB2") (pinfunction "RSB2_RSB2") (pintype "bidirectional"))
    )
    (net (code "198") (name "ZVCCINT") (class "Default")
      (node (ref "C34") (pin "1") (pinfunction "1_1") (pintype "passive"))
      (node (ref "U$7") (pin "VCC") (pinfunction "VCC_VCC") (pintype "bidirectional"))
    )
    (net (code "199") (name "_E-ENDSTOP-C1") (class "Default")
      (node (ref "D20") (pin "C") (pinfunction "C_C") (pintype "passive"))
      (node (ref "J7") (pin "9") (pinfunction "9_9") (pintype "passive"))
    )
    (net (code "200") (name "_X-ENDSTOP-C1") (class "Default")
      (node (ref "D16") (pin "C") (pinfunction "C_C") (pintype "passive"))
      (node (ref "Z-CONN1") (pin "9") (pinfunction "9_9") (pintype "passive"))
    )
    (net (code "201") (name "_Y-ENDSTOP-C1") (class "Default")
      (node (ref "D17") (pin "C") (pinfunction "C_C") (pintype "passive"))
      (node (ref "J6") (pin "9") (pinfunction "9_9") (pintype "passive"))
    )
    (net (code "202") (name "_Z-ENDSTOP-C1") (class "Default")
      (node (ref "D19") (pin "C") (pinfunction "C_C") (pintype "passive"))
      (node (ref "J8") (pin "9") (pinfunction "9_9") (pintype "passive"))
    )
    (net (code "203") (name "unconnected-(IC3-(ICP1)PD4-Pad47)") (class "Default")
      (node (ref "IC3") (pin "47") (pinfunction "(ICP1)PD4_47") (pintype "bidirectional"))
    )
    (net (code "204") (name "unconnected-(IC3-(T1)PD6-Pad49)") (class "Default")
      (node (ref "IC3") (pin "49") (pinfunction "(T1)PD6_49") (pintype "bidirectional"))
    )
    (net (code "205") (name "unconnected-(IC3-(TOSC1)PG4-Pad29)") (class "Default")
      (node (ref "IC3") (pin "29") (pinfunction "(TOSC1)PG4_29") (pintype "bidirectional"))
    )
    (net (code "206") (name "unconnected-(IC3-(TOSC2)PG3-Pad28)") (class "Default")
      (node (ref "IC3") (pin "28") (pinfunction "(TOSC2)PG3_28") (pintype "bidirectional"))
    )
    (net (code "207") (name "unconnected-(IC3-(XCK0{slash}AIN0)PE2-Pad4)") (class "Default")
      (node (ref "IC3") (pin "4") (pinfunction "(XCK0/AIN0)PE2_4") (pintype "bidirectional"))
    )
    (net (code "208") (name "unconnected-(IC3-(XCK1)PD5-Pad48)") (class "Default")
      (node (ref "IC3") (pin "48") (pinfunction "(XCK1)PD5_48") (pintype "bidirectional"))
    )
    (net (code "209") (name "unconnected-(IC3-PH2(XCK2)-Pad14)") (class "Default")
      (node (ref "IC3") (pin "14") (pinfunction "PH2(XCK2)_14") (pintype "bidirectional"))
    )
    (net (code "210") (name "unconnected-(IC3-PH7(T4)-Pad27)") (class "Default")
      (node (ref "IC3") (pin "27") (pinfunction "PH7(T4)_27") (pintype "bidirectional"))
    )
    (net (code "211") (name "unconnected-(IC3-PJ2(XCK3{slash}PCINT11)-Pad65)") (class "Default")
      (node (ref "IC3") (pin "65") (pinfunction "PJ2(XCK3/PCINT11)_65") (pintype "bidirectional"))
    )
    (net (code "212") (name "unconnected-(IC3-PJ3(PCINT12)-Pad66)") (class "Default")
      (node (ref "IC3") (pin "66") (pinfunction "PJ3(PCINT12)_66") (pintype "bidirectional"))
    )
    (net (code "213") (name "unconnected-(IC3-PJ4(PCINT13)-Pad67)") (class "Default")
      (node (ref "IC3") (pin "67") (pinfunction "PJ4(PCINT13)_67") (pintype "bidirectional"))
    )
    (net (code "214") (name "unconnected-(IC3-PJ5(PCINT14)-Pad68)") (class "Default")
      (node (ref "IC3") (pin "68") (pinfunction "PJ5(PCINT14)_68") (pintype "bidirectional"))
    )
    (net (code "215") (name "unconnected-(IC3-PJ6(PCINT15)-Pad69)") (class "Default")
      (node (ref "IC3") (pin "69") (pinfunction "PJ6(PCINT15)_69") (pintype "bidirectional"))
    )
    (net (code "216") (name "unconnected-(IC3-PJ7-Pad79)") (class "Default")
      (node (ref "IC3") (pin "79") (pinfunction "PJ7_79") (pintype "bidirectional"))
    )
    (net (code "217") (name "unconnected-(IC5A-OUT-Pad1)") (class "Default")
      (node (ref "IC5") (pin "1") (pinfunction "OUT_1") (pintype "output"))
    )
    (net (code "218") (name "unconnected-(U$1-PadNC1)") (class "Default")
      (node (ref "U$1") (pin "NC1") (pinfunction "NC1_NC1") (pintype "bidirectional"))
    )
    (net (code "219") (name "unconnected-(U$1-PadNC2)") (class "Default")
      (node (ref "U$1") (pin "NC2") (pinfunction "NC2_NC2") (pintype "bidirectional"))
    )
    (net (code "220") (name "unconnected-(U$1-PadNC3)") (class "Default")
      (node (ref "U$1") (pin "NC3") (pinfunction "NC3_NC3") (pintype "bidirectional"))
    )
    (net (code "221") (name "unconnected-(U$1-PadNC4)") (class "Default")
      (node (ref "U$1") (pin "NC4") (pinfunction "NC4_NC4") (pintype "bidirectional"))
    )
    (net (code "222") (name "unconnected-(U$1-PadNC5)") (class "Default")
      (node (ref "U$1") (pin "NC5") (pinfunction "NC5_NC5") (pintype "bidirectional"))
    )
    (net (code "223") (name "unconnected-(U$1-PadNC6)") (class "Default")
      (node (ref "U$1") (pin "NC6") (pinfunction "NC6_NC6") (pintype "bidirectional"))
    )
    (net (code "224") (name "unconnected-(U$1-PadNC7)") (class "Default")
      (node (ref "U$1") (pin "NC7") (pinfunction "NC7_NC7") (pintype "bidirectional"))
    )
    (net (code "225") (name "unconnected-(U$1-PadNC8)") (class "Default")
      (node (ref "U$1") (pin "NC8") (pinfunction "NC8_NC8") (pintype "bidirectional"))
    )
    (net (code "226") (name "unconnected-(U$1-PadNC9)") (class "Default")
      (node (ref "U$1") (pin "NC9") (pinfunction "NC9_NC9") (pintype "bidirectional"))
    )
    (net (code "227") (name "unconnected-(U$1-PadNC10)") (class "Default")
      (node (ref "U$1") (pin "NC10") (pinfunction "NC10_NC10") (pintype "bidirectional"))
    )
    (net (code "228") (name "unconnected-(U$1-PadNC11)") (class "Default")
      (node (ref "U$1") (pin "NC11") (pinfunction "NC11_NC11") (pintype "bidirectional"))
    )
    (net (code "229") (name "unconnected-(U$1-PadNC12)") (class "Default")
      (node (ref "U$1") (pin "NC12") (pinfunction "NC12_NC12") (pintype "bidirectional"))
    )
    (net (code "230") (name "unconnected-(U$1-PadNC13)") (class "Default")
      (node (ref "U$1") (pin "NC13") (pinfunction "NC13_NC13") (pintype "bidirectional"))
    )
    (net (code "231") (name "unconnected-(U$1-PadNC14)") (class "Default")
      (node (ref "U$1") (pin "NC14") (pinfunction "NC14_NC14") (pintype "bidirectional"))
    )
    (net (code "232") (name "unconnected-(U$1-PadNC15)") (class "Default")
      (node (ref "U$1") (pin "NC15") (pinfunction "NC15_NC15") (pintype "bidirectional"))
    )
    (net (code "233") (name "unconnected-(U$1-PadNC16)") (class "Default")
      (node (ref "U$1") (pin "NC16") (pinfunction "NC16_NC16") (pintype "bidirectional"))
    )
    (net (code "234") (name "unconnected-(U$1-PadRESET)") (class "Default")
      (node (ref "U$1") (pin "RESET") (pinfunction "RESET_RESET") (pintype "bidirectional"))
    )
    (net (code "235") (name "unconnected-(U$2-PadNC1)") (class "Default")
      (node (ref "U$2") (pin "NC1") (pinfunction "NC1_NC1") (pintype "bidirectional"))
    )
    (net (code "236") (name "unconnected-(U$2-PadNC2)") (class "Default")
      (node (ref "U$2") (pin "NC2") (pinfunction "NC2_NC2") (pintype "bidirectional"))
    )
    (net (code "237") (name "unconnected-(U$2-PadNC3)") (class "Default")
      (node (ref "U$2") (pin "NC3") (pinfunction "NC3_NC3") (pintype "bidirectional"))
    )
    (net (code "238") (name "unconnected-(U$2-PadNC4)") (class "Default")
      (node (ref "U$2") (pin "NC4") (pinfunction "NC4_NC4") (pintype "bidirectional"))
    )
    (net (code "239") (name "unconnected-(U$2-PadNC5)") (class "Default")
      (node (ref "U$2") (pin "NC5") (pinfunction "NC5_NC5") (pintype "bidirectional"))
    )
    (net (code "240") (name "unconnected-(U$2-PadNC6)") (class "Default")
      (node (ref "U$2") (pin "NC6") (pinfunction "NC6_NC6") (pintype "bidirectional"))
    )
    (net (code "241") (name "unconnected-(U$2-PadNC7)") (class "Default")
      (node (ref "U$2") (pin "NC7") (pinfunction "NC7_NC7") (pintype "bidirectional"))
    )
    (net (code "242") (name "unconnected-(U$2-PadNC8)") (class "Default")
      (node (ref "U$2") (pin "NC8") (pinfunction "NC8_NC8") (pintype "bidirectional"))
    )
    (net (code "243") (name "unconnected-(U$2-PadNC9)") (class "Default")
      (node (ref "U$2") (pin "NC9") (pinfunction "NC9_NC9") (pintype "bidirectional"))
    )
    (net (code "244") (name "unconnected-(U$2-PadNC10)") (class "Default")
      (node (ref "U$2") (pin "NC10") (pinfunction "NC10_NC10") (pintype "bidirectional"))
    )
    (net (code "245") (name "unconnected-(U$2-PadNC11)") (class "Default")
      (node (ref "U$2") (pin "NC11") (pinfunction "NC11_NC11") (pintype "bidirectional"))
    )
    (net (code "246") (name "unconnected-(U$2-PadNC12)") (class "Default")
      (node (ref "U$2") (pin "NC12") (pinfunction "NC12_NC12") (pintype "bidirectional"))
    )
    (net (code "247") (name "unconnected-(U$2-PadNC13)") (class "Default")
      (node (ref "U$2") (pin "NC13") (pinfunction "NC13_NC13") (pintype "bidirectional"))
    )
    (net (code "248") (name "unconnected-(U$2-PadNC14)") (class "Default")
      (node (ref "U$2") (pin "NC14") (pinfunction "NC14_NC14") (pintype "bidirectional"))
    )
    (net (code "249") (name "unconnected-(U$2-PadNC15)") (class "Default")
      (node (ref "U$2") (pin "NC15") (pinfunction "NC15_NC15") (pintype "bidirectional"))
    )
    (net (code "250") (name "unconnected-(U$2-PadNC16)") (class "Default")
      (node (ref "U$2") (pin "NC16") (pinfunction "NC16_NC16") (pintype "bidirectional"))
    )
    (net (code "251") (name "unconnected-(U$2-PadRESET)") (class "Default")
      (node (ref "U$2") (pin "RESET") (pinfunction "RESET_RESET") (pintype "bidirectional"))
    )
    (net (code "252") (name "unconnected-(U$7-PadNC1)") (class "Default")
      (node (ref "U$7") (pin "NC1") (pinfunction "NC1_NC1") (pintype "bidirectional"))
    )
    (net (code "253") (name "unconnected-(U$7-PadNC2)") (class "Default")
      (node (ref "U$7") (pin "NC2") (pinfunction "NC2_NC2") (pintype "bidirectional"))
    )
    (net (code "254") (name "unconnected-(U$7-PadNC3)") (class "Default")
      (node (ref "U$7") (pin "NC3") (pinfunction "NC3_NC3") (pintype "bidirectional"))
    )
    (net (code "255") (name "unconnected-(U$7-PadNC4)") (class "Default")
      (node (ref "U$7") (pin "NC4") (pinfunction "NC4_NC4") (pintype "bidirectional"))
    )
    (net (code "256") (name "unconnected-(U$7-PadNC5)") (class "Default")
      (node (ref "U$7") (pin "NC5") (pinfunction "NC5_NC5") (pintype "bidirectional"))
    )
    (net (code "257") (name "unconnected-(U$7-PadNC6)") (class "Default")
      (node (ref "U$7") (pin "NC6") (pinfunction "NC6_NC6") (pintype "bidirectional"))
    )
    (net (code "258") (name "unconnected-(U$7-PadNC7)") (class "Default")
      (node (ref "U$7") (pin "NC7") (pinfunction "NC7_NC7") (pintype "bidirectional"))
    )
    (net (code "259") (name "unconnected-(U$7-PadNC8)") (class "Default")
      (node (ref "U$7") (pin "NC8") (pinfunction "NC8_NC8") (pintype "bidirectional"))
    )
    (net (code "260") (name "unconnected-(U$7-PadNC9)") (class "Default")
      (node (ref "U$7") (pin "NC9") (pinfunction "NC9_NC9") (pintype "bidirectional"))
    )
    (net (code "261") (name "unconnected-(U$7-PadNC10)") (class "Default")
      (node (ref "U$7") (pin "NC10") (pinfunction "NC10_NC10") (pintype "bidirectional"))
    )
    (net (code "262") (name "unconnected-(U$7-PadNC11)") (class "Default")
      (node (ref "U$7") (pin "NC11") (pinfunction "NC11_NC11") (pintype "bidirectional"))
    )
    (net (code "263") (name "unconnected-(U$7-PadNC12)") (class "Default")
      (node (ref "U$7") (pin "NC12") (pinfunction "NC12_NC12") (pintype "bidirectional"))
    )
    (net (code "264") (name "unconnected-(U$7-PadNC13)") (class "Default")
      (node (ref "U$7") (pin "NC13") (pinfunction "NC13_NC13") (pintype "bidirectional"))
    )
    (net (code "265") (name "unconnected-(U$7-PadNC14)") (class "Default")
      (node (ref "U$7") (pin "NC14") (pinfunction "NC14_NC14") (pintype "bidirectional"))
    )
    (net (code "266") (name "unconnected-(U$7-PadNC15)") (class "Default")
      (node (ref "U$7") (pin "NC15") (pinfunction "NC15_NC15") (pintype "bidirectional"))
    )
    (net (code "267") (name "unconnected-(U$7-PadNC16)") (class "Default")
      (node (ref "U$7") (pin "NC16") (pinfunction "NC16_NC16") (pintype "bidirectional"))
    )
    (net (code "268") (name "unconnected-(U$7-PadRESET)") (class "Default")
      (node (ref "U$7") (pin "RESET") (pinfunction "RESET_RESET") (pintype "bidirectional"))
    )
    (net (code "269") (name "unconnected-(U$17-PadNC1)") (class "Default")
      (node (ref "U$17") (pin "NC1") (pinfunction "NC1_NC1") (pintype "bidirectional"))
    )
    (net (code "270") (name "unconnected-(U$17-PadNC2)") (class "Default")
      (node (ref "U$17") (pin "NC2") (pinfunction "NC2_NC2") (pintype "bidirectional"))
    )
    (net (code "271") (name "unconnected-(U$17-PadNC3)") (class "Default")
      (node (ref "U$17") (pin "NC3") (pinfunction "NC3_NC3") (pintype "bidirectional"))
    )
    (net (code "272") (name "unconnected-(U$17-PadNC4)") (class "Default")
      (node (ref "U$17") (pin "NC4") (pinfunction "NC4_NC4") (pintype "bidirectional"))
    )
    (net (code "273") (name "unconnected-(U$17-PadNC5)") (class "Default")
      (node (ref "U$17") (pin "NC5") (pinfunction "NC5_NC5") (pintype "bidirectional"))
    )
    (net (code "274") (name "unconnected-(U$17-PadNC6)") (class "Default")
      (node (ref "U$17") (pin "NC6") (pinfunction "NC6_NC6") (pintype "bidirectional"))
    )
    (net (code "275") (name "unconnected-(U$17-PadNC7)") (class "Default")
      (node (ref "U$17") (pin "NC7") (pinfunction "NC7_NC7") (pintype "bidirectional"))
    )
    (net (code "276") (name "unconnected-(U$17-PadNC8)") (class "Default")
      (node (ref "U$17") (pin "NC8") (pinfunction "NC8_NC8") (pintype "bidirectional"))
    )
    (net (code "277") (name "unconnected-(U$17-PadNC9)") (class "Default")
      (node (ref "U$17") (pin "NC9") (pinfunction "NC9_NC9") (pintype "bidirectional"))
    )
    (net (code "278") (name "unconnected-(U$17-PadNC10)") (class "Default")
      (node (ref "U$17") (pin "NC10") (pinfunction "NC10_NC10") (pintype "bidirectional"))
    )
    (net (code "279") (name "unconnected-(U$17-PadNC11)") (class "Default")
      (node (ref "U$17") (pin "NC11") (pinfunction "NC11_NC11") (pintype "bidirectional"))
    )
    (net (code "280") (name "unconnected-(U$17-PadNC12)") (class "Default")
      (node (ref "U$17") (pin "NC12") (pinfunction "NC12_NC12") (pintype "bidirectional"))
    )
    (net (code "281") (name "unconnected-(U$17-PadNC13)") (class "Default")
      (node (ref "U$17") (pin "NC13") (pinfunction "NC13_NC13") (pintype "bidirectional"))
    )
    (net (code "282") (name "unconnected-(U$17-PadNC14)") (class "Default")
      (node (ref "U$17") (pin "NC14") (pinfunction "NC14_NC14") (pintype "bidirectional"))
    )
    (net (code "283") (name "unconnected-(U$17-PadNC15)") (class "Default")
      (node (ref "U$17") (pin "NC15") (pinfunction "NC15_NC15") (pintype "bidirectional"))
    )
    (net (code "284") (name "unconnected-(U$17-PadNC16)") (class "Default")
      (node (ref "U$17") (pin "NC16") (pinfunction "NC16_NC16") (pintype "bidirectional"))
    )
    (net (code "285") (name "unconnected-(U$17-PadRESET)") (class "Default")
      (node (ref "U$17") (pin "RESET") (pinfunction "RESET_RESET") (pintype "bidirectional"))
    )
    (net (code "286") (name "unconnected-(U2-NC-Pad1)") (class "Default")
      (node (ref "U2") (pin "1") (pinfunction "NC_1") (pintype "bidirectional"))
    )
    (net (code "287") (name "unconnected-(U2-RSV-Pad8)") (class "Default")
      (node (ref "U2") (pin "8") (pinfunction "RSV_8") (pintype "bidirectional"))
    )
    (net (code "288") (name "unconnected-(U2-SHIELD-PadCDNC1)") (class "Default")
      (node (ref "U2") (pin "CDNC1") (pinfunction "SHIELD_CDNC1") (pintype "bidirectional"))
    )
    (net (code "289") (name "unconnected-(U2-SHIELD-PadCDNC2)") (class "Default")
      (node (ref "U2") (pin "CDNC2") (pinfunction "SHIELD_CDNC2") (pintype "bidirectional"))
    )
    (net (code "290") (name "unconnected-(U6-DCD-Pad10)") (class "Default")
      (node (ref "U6") (pin "10") (pinfunction "DCD_10") (pintype "input"))
    )
    (net (code "291") (name "unconnected-(U6-DSR-Pad9)") (class "Default")
      (node (ref "U6") (pin "9") (pinfunction "DSR_9") (pintype "input"))
    )
    (net (code "292") (name "unconnected-(U6-OSCI-Pad27)") (class "Default")
      (node (ref "U6") (pin "27") (pinfunction "OSCI_27") (pintype "input"))
    )
    (net (code "293") (name "unconnected-(U6-OSCO-Pad28)") (class "Default")
      (node (ref "U6") (pin "28") (pinfunction "OSCO_28") (pintype "output"))
    )
    (net (code "294") (name "unconnected-(U6-PWREN-Pad14)") (class "Default")
      (node (ref "U6") (pin "14") (pinfunction "PWREN_14") (pintype "input"))
    )
    (net (code "295") (name "unconnected-(U6-RESET-Pad19)") (class "Default")
      (node (ref "U6") (pin "19") (pinfunction "RESET_19") (pintype "input"))
    )
    (net (code "296") (name "unconnected-(U6-RI-Pad6)") (class "Default")
      (node (ref "U6") (pin "6") (pinfunction "RI_6") (pintype "input"))
    )
    (net (code "297") (name "unconnected-(U6-SLEEP-Pad12)") (class "Default")
      (node (ref "U6") (pin "12") (pinfunction "SLEEP_12") (pintype "input"))
    )
    (net (code "298") (name "unconnected-(U6-TXDEN-Pad13)") (class "Default")
      (node (ref "U6") (pin "13") (pinfunction "TXDEN_13") (pintype "input"))
    )
  )
)
